# VmeConnectors.net
KiCad netlist of a schematic drawn in Altium Designer
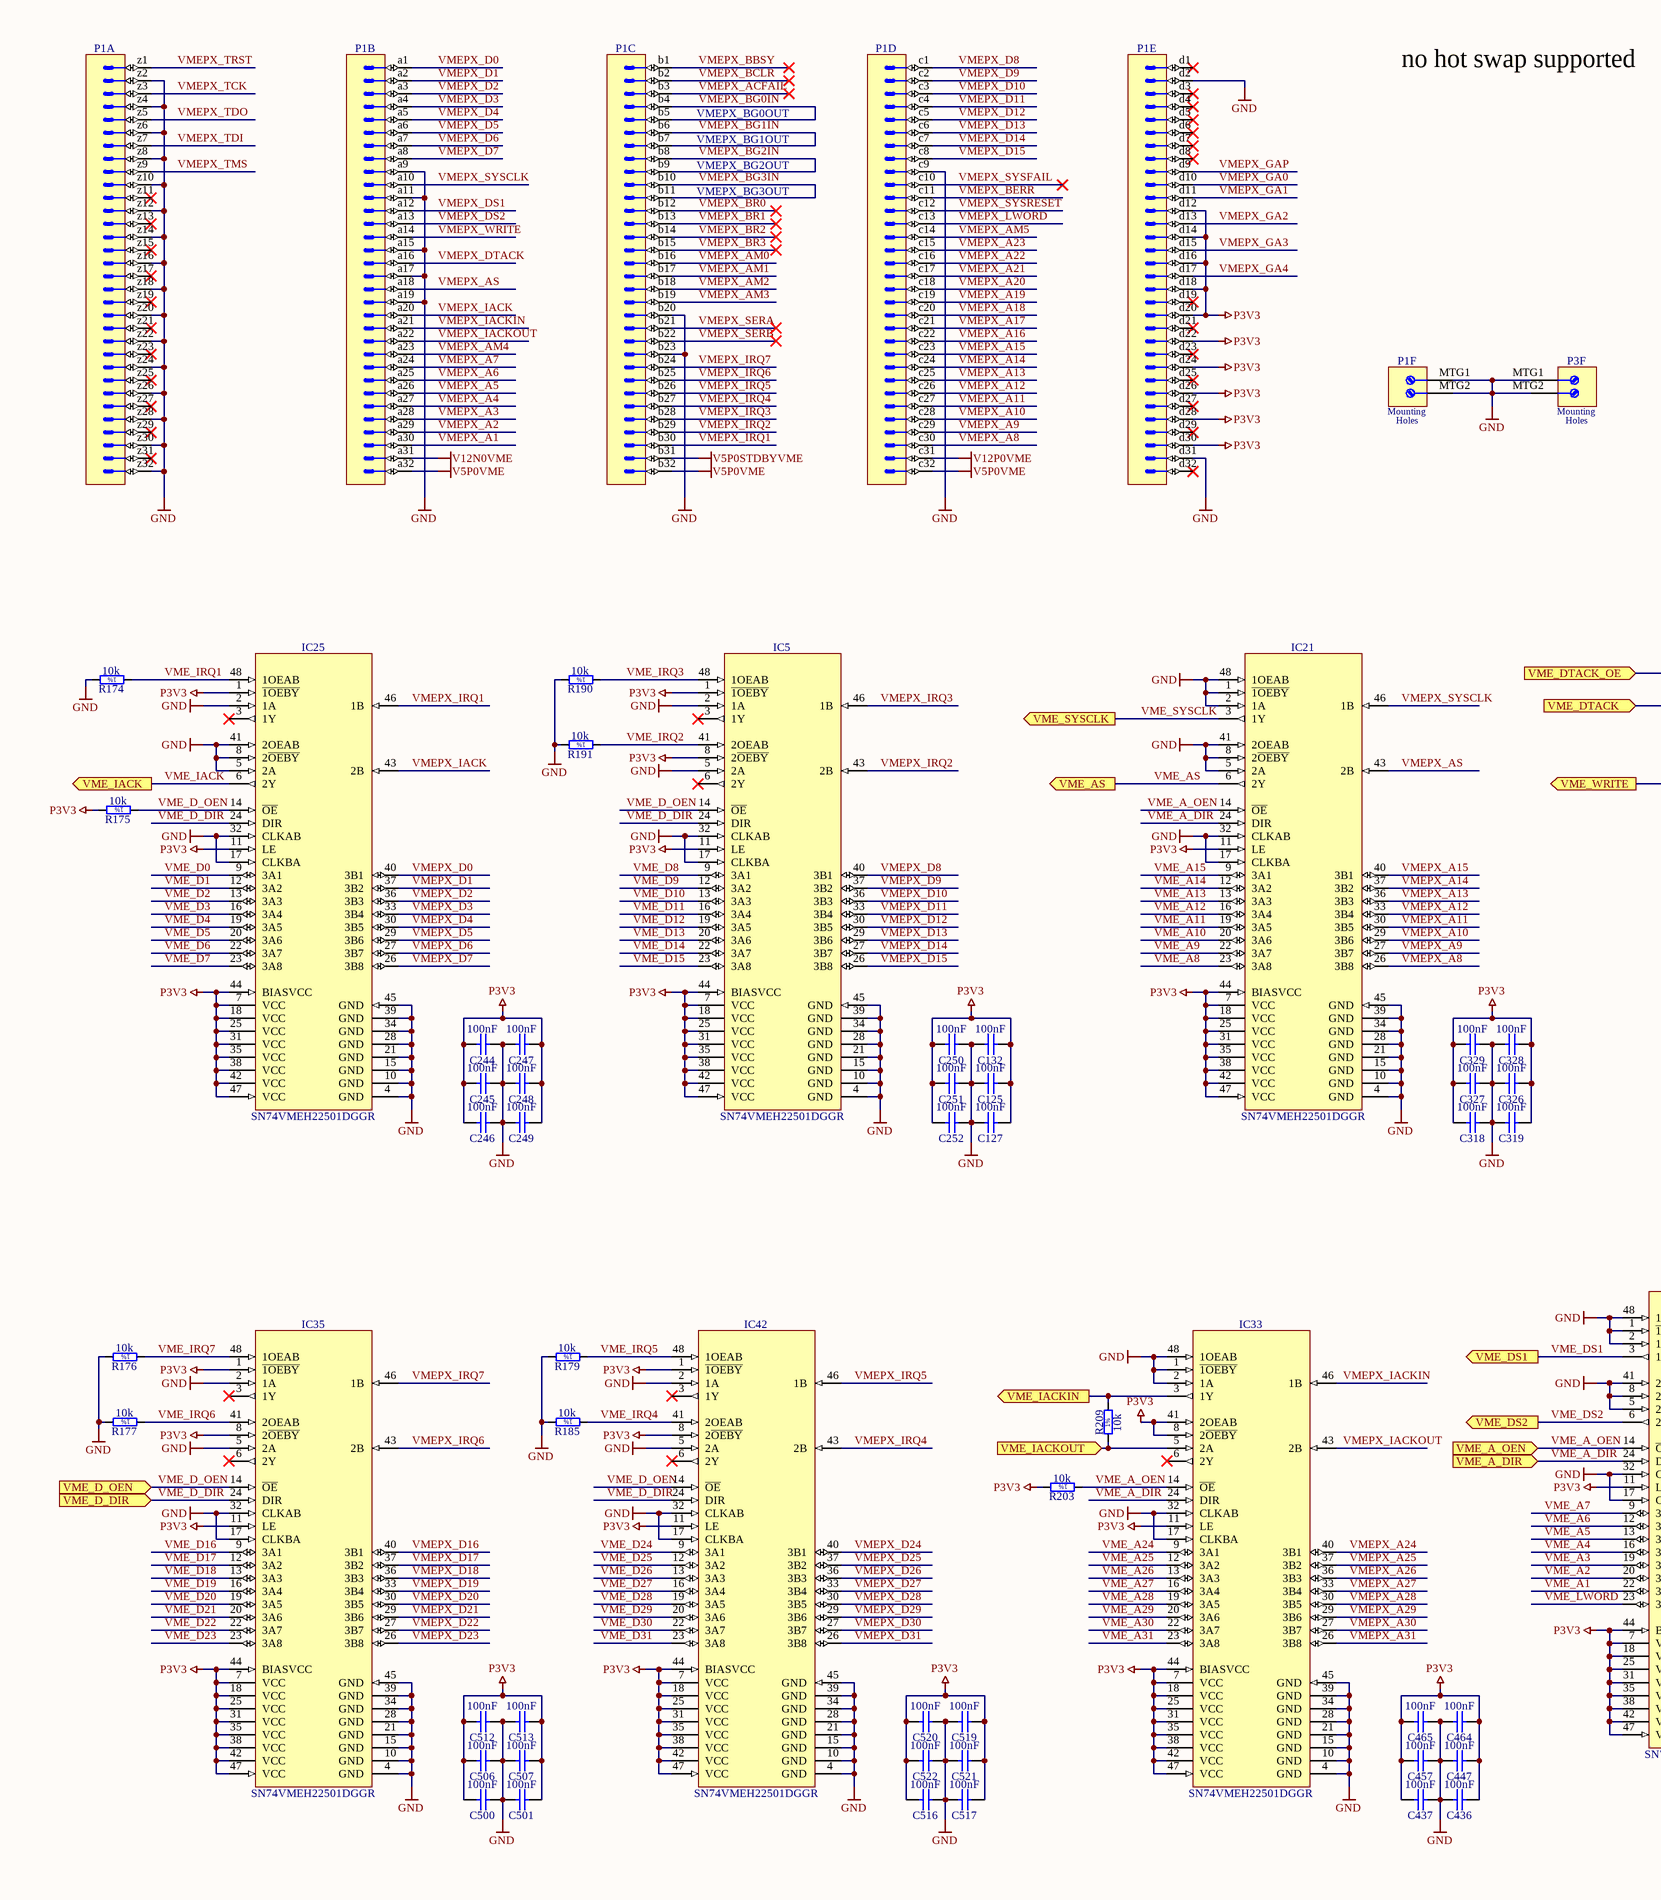
[diagram p0: VmeConnectors.SchDoc, left]
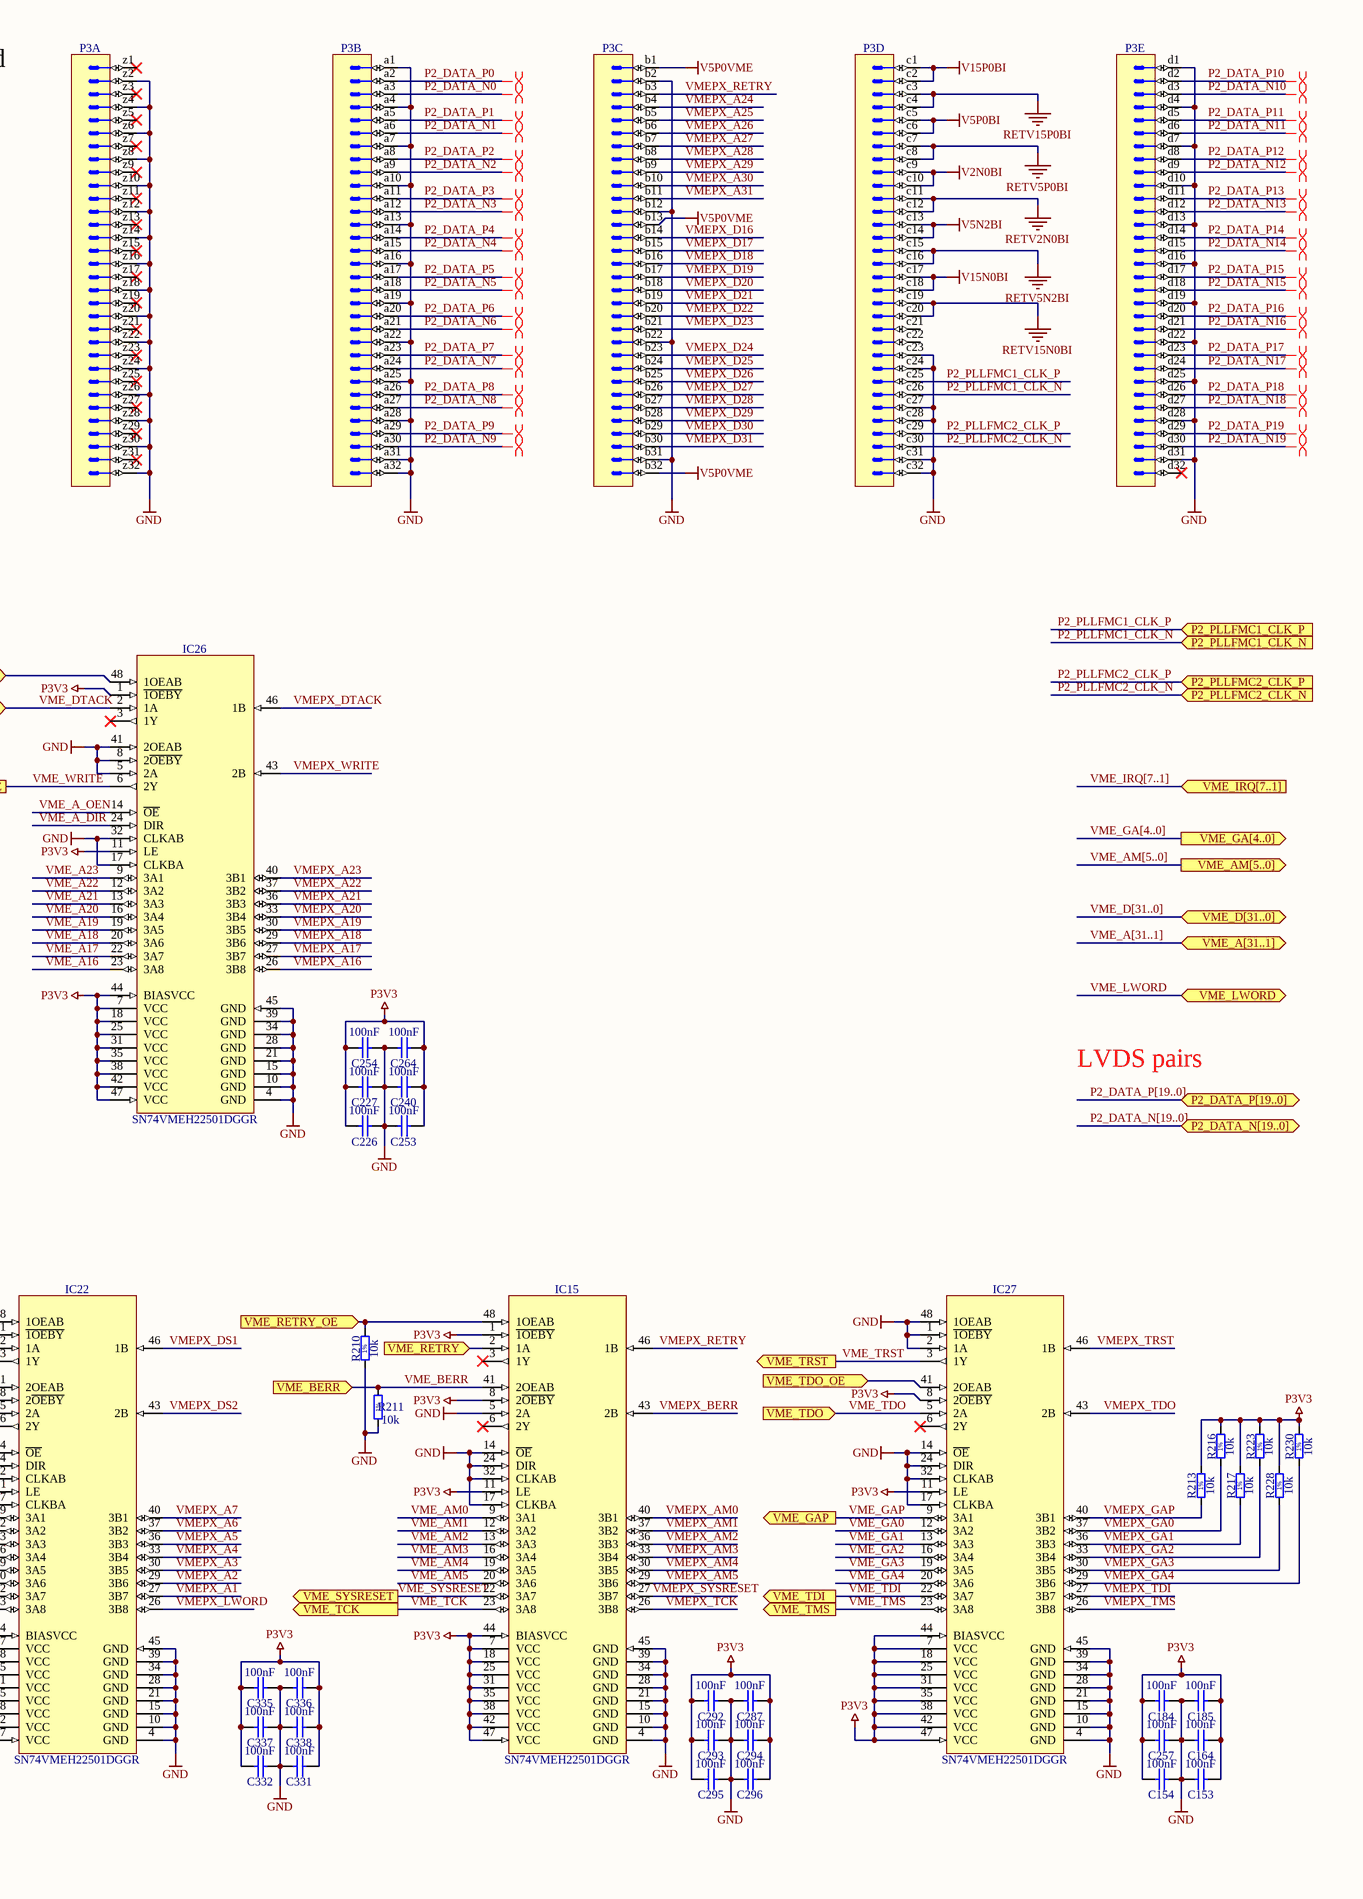
[diagram p1: VmeConnectors.SchDoc, right]

(export (version "E")
  (design (tool "Eeschema 10.0.6"))
  (components
    (comp (ref "C125")
      (value "100nF")
      (footprint "CAPC1005X55N")
      (description "Non-polarised capacitor")
      (fields
        (field (name "PART NUMBER") "CC0402_100NF_16V_10%_X7R")
        (field (name "VOLTAGE") "16V")
        (field (name "AUTHOR") "CERN DEM JLC")
      )
      (libsource (lib "Capacitors") (part "Capacitor - non polarized"))
    )
    (comp (ref "C127")
      (value "100nF")
      (footprint "CAPC1005X55N")
      (description "Non-polarised capacitor")
      (fields
        (field (name "PART NUMBER") "CC0402_100NF_16V_10%_X7R")
        (field (name "VOLTAGE") "16V")
        (field (name "AUTHOR") "CERN DEM JLC")
      )
      (libsource (lib "Capacitors") (part "Capacitor - non polarized"))
    )
    (comp (ref "C132")
      (value "100nF")
      (footprint "CAPC1005X55N")
      (description "Non-polarised capacitor")
      (fields
        (field (name "PART NUMBER") "CC0402_100NF_16V_10%_X7R")
        (field (name "VOLTAGE") "16V")
        (field (name "AUTHOR") "CERN DEM JLC")
      )
      (libsource (lib "Capacitors") (part "Capacitor - non polarized"))
    )
    (comp (ref "C153")
      (value "100nF")
      (footprint "CAPC1005X55N")
      (description "Non-polarised capacitor")
      (fields
        (field (name "PART NUMBER") "CC0402_100NF_16V_10%_X7R")
        (field (name "VOLTAGE") "16V")
        (field (name "AUTHOR") "CERN DEM JLC")
      )
      (libsource (lib "Capacitors") (part "Capacitor - non polarized"))
    )
    (comp (ref "C154")
      (value "100nF")
      (footprint "CAPC1005X55N")
      (description "Non-polarised capacitor")
      (fields
        (field (name "PART NUMBER") "CC0402_100NF_16V_10%_X7R")
        (field (name "VOLTAGE") "16V")
        (field (name "AUTHOR") "CERN DEM JLC")
      )
      (libsource (lib "Capacitors") (part "Capacitor - non polarized"))
    )
    (comp (ref "C164")
      (value "100nF")
      (footprint "CAPC1005X55N")
      (description "Non-polarised capacitor")
      (fields
        (field (name "PART NUMBER") "CC0402_100NF_16V_10%_X7R")
        (field (name "VOLTAGE") "16V")
        (field (name "AUTHOR") "CERN DEM JLC")
      )
      (libsource (lib "Capacitors") (part "Capacitor - non polarized"))
    )
    (comp (ref "C184")
      (value "100nF")
      (footprint "CAPC1005X55N")
      (description "Non-polarised capacitor")
      (fields
        (field (name "PART NUMBER") "CC0402_100NF_16V_10%_X7R")
        (field (name "VOLTAGE") "16V")
        (field (name "AUTHOR") "CERN DEM JLC")
      )
      (libsource (lib "Capacitors") (part "Capacitor - non polarized"))
    )
    (comp (ref "C185")
      (value "100nF")
      (footprint "CAPC1005X55N")
      (description "Non-polarised capacitor")
      (fields
        (field (name "PART NUMBER") "CC0402_100NF_16V_10%_X7R")
        (field (name "VOLTAGE") "16V")
        (field (name "AUTHOR") "CERN DEM JLC")
      )
      (libsource (lib "Capacitors") (part "Capacitor - non polarized"))
    )
    (comp (ref "C226")
      (value "100nF")
      (footprint "CAPC1005X55N")
      (description "Non-polarised capacitor")
      (fields
        (field (name "PART NUMBER") "CC0402_100NF_16V_10%_X7R")
        (field (name "VOLTAGE") "16V")
        (field (name "AUTHOR") "CERN DEM JLC")
      )
      (libsource (lib "Capacitors") (part "Capacitor - non polarized"))
    )
    (comp (ref "C227")
      (value "100nF")
      (footprint "CAPC1005X55N")
      (description "Non-polarised capacitor")
      (fields
        (field (name "PART NUMBER") "CC0402_100NF_16V_10%_X7R")
        (field (name "VOLTAGE") "16V")
        (field (name "AUTHOR") "CERN DEM JLC")
      )
      (libsource (lib "Capacitors") (part "Capacitor - non polarized"))
    )
    (comp (ref "C240")
      (value "100nF")
      (footprint "CAPC1005X55N")
      (description "Non-polarised capacitor")
      (fields
        (field (name "PART NUMBER") "CC0402_100NF_16V_10%_X7R")
        (field (name "VOLTAGE") "16V")
        (field (name "AUTHOR") "CERN DEM JLC")
      )
      (libsource (lib "Capacitors") (part "Capacitor - non polarized"))
    )
    (comp (ref "C244")
      (value "100nF")
      (footprint "CAPC1005X55N")
      (description "Non-polarised capacitor")
      (fields
        (field (name "PART NUMBER") "CC0402_100NF_16V_10%_X7R")
        (field (name "VOLTAGE") "16V")
        (field (name "AUTHOR") "CERN DEM JLC")
      )
      (libsource (lib "Capacitors") (part "Capacitor - non polarized"))
    )
    (comp (ref "C245")
      (value "100nF")
      (footprint "CAPC1005X55N")
      (description "Non-polarised capacitor")
      (fields
        (field (name "PART NUMBER") "CC0402_100NF_16V_10%_X7R")
        (field (name "VOLTAGE") "16V")
        (field (name "AUTHOR") "CERN DEM JLC")
      )
      (libsource (lib "Capacitors") (part "Capacitor - non polarized"))
    )
    (comp (ref "C246")
      (value "100nF")
      (footprint "CAPC1005X55N")
      (description "Non-polarised capacitor")
      (fields
        (field (name "PART NUMBER") "CC0402_100NF_16V_10%_X7R")
        (field (name "VOLTAGE") "16V")
        (field (name "AUTHOR") "CERN DEM JLC")
      )
      (libsource (lib "Capacitors") (part "Capacitor - non polarized"))
    )
    (comp (ref "C247")
      (value "100nF")
      (footprint "CAPC1005X55N")
      (description "Non-polarised capacitor")
      (fields
        (field (name "PART NUMBER") "CC0402_100NF_16V_10%_X7R")
        (field (name "VOLTAGE") "16V")
        (field (name "AUTHOR") "CERN DEM JLC")
      )
      (libsource (lib "Capacitors") (part "Capacitor - non polarized"))
    )
    (comp (ref "C248")
      (value "100nF")
      (footprint "CAPC1005X55N")
      (description "Non-polarised capacitor")
      (fields
        (field (name "PART NUMBER") "CC0402_100NF_16V_10%_X7R")
        (field (name "VOLTAGE") "16V")
        (field (name "AUTHOR") "CERN DEM JLC")
      )
      (libsource (lib "Capacitors") (part "Capacitor - non polarized"))
    )
    (comp (ref "C249")
      (value "100nF")
      (footprint "CAPC1005X55N")
      (description "Non-polarised capacitor")
      (fields
        (field (name "PART NUMBER") "CC0402_100NF_16V_10%_X7R")
        (field (name "VOLTAGE") "16V")
        (field (name "AUTHOR") "CERN DEM JLC")
      )
      (libsource (lib "Capacitors") (part "Capacitor - non polarized"))
    )
    (comp (ref "C250")
      (value "100nF")
      (footprint "CAPC1005X55N")
      (description "Non-polarised capacitor")
      (fields
        (field (name "PART NUMBER") "CC0402_100NF_16V_10%_X7R")
        (field (name "VOLTAGE") "16V")
        (field (name "AUTHOR") "CERN DEM JLC")
      )
      (libsource (lib "Capacitors") (part "Capacitor - non polarized"))
    )
    (comp (ref "C251")
      (value "100nF")
      (footprint "CAPC1005X55N")
      (description "Non-polarised capacitor")
      (fields
        (field (name "PART NUMBER") "CC0402_100NF_16V_10%_X7R")
        (field (name "VOLTAGE") "16V")
        (field (name "AUTHOR") "CERN DEM JLC")
      )
      (libsource (lib "Capacitors") (part "Capacitor - non polarized"))
    )
    (comp (ref "C252")
      (value "100nF")
      (footprint "CAPC1005X55N")
      (description "Non-polarised capacitor")
      (fields
        (field (name "PART NUMBER") "CC0402_100NF_16V_10%_X7R")
        (field (name "VOLTAGE") "16V")
        (field (name "AUTHOR") "CERN DEM JLC")
      )
      (libsource (lib "Capacitors") (part "Capacitor - non polarized"))
    )
    (comp (ref "C253")
      (value "100nF")
      (footprint "CAPC1005X55N")
      (description "Non-polarised capacitor")
      (fields
        (field (name "PART NUMBER") "CC0402_100NF_16V_10%_X7R")
        (field (name "VOLTAGE") "16V")
        (field (name "AUTHOR") "CERN DEM JLC")
      )
      (libsource (lib "Capacitors") (part "Capacitor - non polarized"))
    )
    (comp (ref "C254")
      (value "100nF")
      (footprint "CAPC1005X55N")
      (description "Non-polarised capacitor")
      (fields
        (field (name "PART NUMBER") "CC0402_100NF_16V_10%_X7R")
        (field (name "VOLTAGE") "16V")
        (field (name "AUTHOR") "CERN DEM JLC")
      )
      (libsource (lib "Capacitors") (part "Capacitor - non polarized"))
    )
    (comp (ref "C257")
      (value "100nF")
      (footprint "CAPC1005X55N")
      (description "Non-polarised capacitor")
      (fields
        (field (name "PART NUMBER") "CC0402_100NF_16V_10%_X7R")
        (field (name "VOLTAGE") "16V")
        (field (name "AUTHOR") "CERN DEM JLC")
      )
      (libsource (lib "Capacitors") (part "Capacitor - non polarized"))
    )
    (comp (ref "C264")
      (value "100nF")
      (footprint "CAPC1005X55N")
      (description "Non-polarised capacitor")
      (fields
        (field (name "PART NUMBER") "CC0402_100NF_16V_10%_X7R")
        (field (name "VOLTAGE") "16V")
        (field (name "AUTHOR") "CERN DEM JLC")
      )
      (libsource (lib "Capacitors") (part "Capacitor - non polarized"))
    )
    (comp (ref "C287")
      (value "100nF")
      (footprint "CAPC1005X55N")
      (description "Non-polarised capacitor")
      (fields
        (field (name "PART NUMBER") "CC0402_100NF_16V_10%_X7R")
        (field (name "VOLTAGE") "16V")
        (field (name "AUTHOR") "CERN DEM JLC")
      )
      (libsource (lib "Capacitors") (part "Capacitor - non polarized"))
    )
    (comp (ref "C292")
      (value "100nF")
      (footprint "CAPC1005X55N")
      (description "Non-polarised capacitor")
      (fields
        (field (name "PART NUMBER") "CC0402_100NF_16V_10%_X7R")
        (field (name "VOLTAGE") "16V")
        (field (name "AUTHOR") "CERN DEM JLC")
      )
      (libsource (lib "Capacitors") (part "Capacitor - non polarized"))
    )
    (comp (ref "C293")
      (value "100nF")
      (footprint "CAPC1005X55N")
      (description "Non-polarised capacitor")
      (fields
        (field (name "PART NUMBER") "CC0402_100NF_16V_10%_X7R")
        (field (name "VOLTAGE") "16V")
        (field (name "AUTHOR") "CERN DEM JLC")
      )
      (libsource (lib "Capacitors") (part "Capacitor - non polarized"))
    )
    (comp (ref "C294")
      (value "100nF")
      (footprint "CAPC1005X55N")
      (description "Non-polarised capacitor")
      (fields
        (field (name "PART NUMBER") "CC0402_100NF_16V_10%_X7R")
        (field (name "VOLTAGE") "16V")
        (field (name "AUTHOR") "CERN DEM JLC")
      )
      (libsource (lib "Capacitors") (part "Capacitor - non polarized"))
    )
    (comp (ref "C295")
      (value "100nF")
      (footprint "CAPC1005X55N")
      (description "Non-polarised capacitor")
      (fields
        (field (name "PART NUMBER") "CC0402_100NF_16V_10%_X7R")
        (field (name "VOLTAGE") "16V")
        (field (name "AUTHOR") "CERN DEM JLC")
      )
      (libsource (lib "Capacitors") (part "Capacitor - non polarized"))
    )
    (comp (ref "C296")
      (value "100nF")
      (footprint "CAPC1005X55N")
      (description "Non-polarised capacitor")
      (fields
        (field (name "PART NUMBER") "CC0402_100NF_16V_10%_X7R")
        (field (name "VOLTAGE") "16V")
        (field (name "AUTHOR") "CERN DEM JLC")
      )
      (libsource (lib "Capacitors") (part "Capacitor - non polarized"))
    )
    (comp (ref "C318")
      (value "100nF")
      (footprint "CAPC1005X55N")
      (description "Non-polarised capacitor")
      (fields
        (field (name "PART NUMBER") "CC0402_100NF_16V_10%_X7R")
        (field (name "VOLTAGE") "16V")
        (field (name "AUTHOR") "CERN DEM JLC")
      )
      (libsource (lib "Capacitors") (part "Capacitor - non polarized"))
    )
    (comp (ref "C319")
      (value "100nF")
      (footprint "CAPC1005X55N")
      (description "Non-polarised capacitor")
      (fields
        (field (name "PART NUMBER") "CC0402_100NF_16V_10%_X7R")
        (field (name "VOLTAGE") "16V")
        (field (name "AUTHOR") "CERN DEM JLC")
      )
      (libsource (lib "Capacitors") (part "Capacitor - non polarized"))
    )
    (comp (ref "C326")
      (value "100nF")
      (footprint "CAPC1005X55N")
      (description "Non-polarised capacitor")
      (fields
        (field (name "PART NUMBER") "CC0402_100NF_16V_10%_X7R")
        (field (name "VOLTAGE") "16V")
        (field (name "AUTHOR") "CERN DEM JLC")
      )
      (libsource (lib "Capacitors") (part "Capacitor - non polarized"))
    )
    (comp (ref "C327")
      (value "100nF")
      (footprint "CAPC1005X55N")
      (description "Non-polarised capacitor")
      (fields
        (field (name "PART NUMBER") "CC0402_100NF_16V_10%_X7R")
        (field (name "VOLTAGE") "16V")
        (field (name "AUTHOR") "CERN DEM JLC")
      )
      (libsource (lib "Capacitors") (part "Capacitor - non polarized"))
    )
    (comp (ref "C328")
      (value "100nF")
      (footprint "CAPC1005X55N")
      (description "Non-polarised capacitor")
      (fields
        (field (name "PART NUMBER") "CC0402_100NF_16V_10%_X7R")
        (field (name "VOLTAGE") "16V")
        (field (name "AUTHOR") "CERN DEM JLC")
      )
      (libsource (lib "Capacitors") (part "Capacitor - non polarized"))
    )
    (comp (ref "C329")
      (value "100nF")
      (footprint "CAPC1005X55N")
      (description "Non-polarised capacitor")
      (fields
        (field (name "PART NUMBER") "CC0402_100NF_16V_10%_X7R")
        (field (name "VOLTAGE") "16V")
        (field (name "AUTHOR") "CERN DEM JLC")
      )
      (libsource (lib "Capacitors") (part "Capacitor - non polarized"))
    )
    (comp (ref "C331")
      (value "100nF")
      (footprint "CAPC1005X55N")
      (description "Non-polarised capacitor")
      (fields
        (field (name "PART NUMBER") "CC0402_100NF_16V_10%_X7R")
        (field (name "VOLTAGE") "16V")
        (field (name "AUTHOR") "CERN DEM JLC")
      )
      (libsource (lib "Capacitors") (part "Capacitor - non polarized"))
    )
    (comp (ref "C332")
      (value "100nF")
      (footprint "CAPC1005X55N")
      (description "Non-polarised capacitor")
      (fields
        (field (name "PART NUMBER") "CC0402_100NF_16V_10%_X7R")
        (field (name "VOLTAGE") "16V")
        (field (name "AUTHOR") "CERN DEM JLC")
      )
      (libsource (lib "Capacitors") (part "Capacitor - non polarized"))
    )
    (comp (ref "C335")
      (value "100nF")
      (footprint "CAPC1005X55N")
      (description "Non-polarised capacitor")
      (fields
        (field (name "PART NUMBER") "CC0402_100NF_16V_10%_X7R")
        (field (name "VOLTAGE") "16V")
        (field (name "AUTHOR") "CERN DEM JLC")
      )
      (libsource (lib "Capacitors") (part "Capacitor - non polarized"))
    )
    (comp (ref "C336")
      (value "100nF")
      (footprint "CAPC1005X55N")
      (description "Non-polarised capacitor")
      (fields
        (field (name "PART NUMBER") "CC0402_100NF_16V_10%_X7R")
        (field (name "VOLTAGE") "16V")
        (field (name "AUTHOR") "CERN DEM JLC")
      )
      (libsource (lib "Capacitors") (part "Capacitor - non polarized"))
    )
    (comp (ref "C337")
      (value "100nF")
      (footprint "CAPC1005X55N")
      (description "Non-polarised capacitor")
      (fields
        (field (name "PART NUMBER") "CC0402_100NF_16V_10%_X7R")
        (field (name "VOLTAGE") "16V")
        (field (name "AUTHOR") "CERN DEM JLC")
      )
      (libsource (lib "Capacitors") (part "Capacitor - non polarized"))
    )
    (comp (ref "C338")
      (value "100nF")
      (footprint "CAPC1005X55N")
      (description "Non-polarised capacitor")
      (fields
        (field (name "PART NUMBER") "CC0402_100NF_16V_10%_X7R")
        (field (name "VOLTAGE") "16V")
        (field (name "AUTHOR") "CERN DEM JLC")
      )
      (libsource (lib "Capacitors") (part "Capacitor - non polarized"))
    )
    (comp (ref "C436")
      (value "100nF")
      (footprint "CAPC1005X55N")
      (description "Non-polarised capacitor")
      (fields
        (field (name "PART NUMBER") "CC0402_100NF_16V_10%_X7R")
        (field (name "VOLTAGE") "16V")
        (field (name "AUTHOR") "CERN DEM JLC")
      )
      (libsource (lib "Capacitors") (part "Capacitor - non polarized"))
    )
    (comp (ref "C437")
      (value "100nF")
      (footprint "CAPC1005X55N")
      (description "Non-polarised capacitor")
      (fields
        (field (name "PART NUMBER") "CC0402_100NF_16V_10%_X7R")
        (field (name "VOLTAGE") "16V")
        (field (name "AUTHOR") "CERN DEM JLC")
      )
      (libsource (lib "Capacitors") (part "Capacitor - non polarized"))
    )
    (comp (ref "C447")
      (value "100nF")
      (footprint "CAPC1005X55N")
      (description "Non-polarised capacitor")
      (fields
        (field (name "PART NUMBER") "CC0402_100NF_16V_10%_X7R")
        (field (name "VOLTAGE") "16V")
        (field (name "AUTHOR") "CERN DEM JLC")
      )
      (libsource (lib "Capacitors") (part "Capacitor - non polarized"))
    )
    (comp (ref "C457")
      (value "100nF")
      (footprint "CAPC1005X55N")
      (description "Non-polarised capacitor")
      (fields
        (field (name "PART NUMBER") "CC0402_100NF_16V_10%_X7R")
        (field (name "VOLTAGE") "16V")
        (field (name "AUTHOR") "CERN DEM JLC")
      )
      (libsource (lib "Capacitors") (part "Capacitor - non polarized"))
    )
    (comp (ref "C464")
      (value "100nF")
      (footprint "CAPC1005X55N")
      (description "Non-polarised capacitor")
      (fields
        (field (name "PART NUMBER") "CC0402_100NF_16V_10%_X7R")
        (field (name "VOLTAGE") "16V")
        (field (name "AUTHOR") "CERN DEM JLC")
      )
      (libsource (lib "Capacitors") (part "Capacitor - non polarized"))
    )
    (comp (ref "C465")
      (value "100nF")
      (footprint "CAPC1005X55N")
      (description "Non-polarised capacitor")
      (fields
        (field (name "PART NUMBER") "CC0402_100NF_16V_10%_X7R")
        (field (name "VOLTAGE") "16V")
        (field (name "AUTHOR") "CERN DEM JLC")
      )
      (libsource (lib "Capacitors") (part "Capacitor - non polarized"))
    )
    (comp (ref "C500")
      (value "100nF")
      (footprint "CAPC1005X55N")
      (description "Non-polarised capacitor")
      (fields
        (field (name "PART NUMBER") "CC0402_100NF_16V_10%_X7R")
        (field (name "VOLTAGE") "16V")
        (field (name "AUTHOR") "CERN DEM JLC")
      )
      (libsource (lib "Capacitors") (part "Capacitor - non polarized"))
    )
    (comp (ref "C501")
      (value "100nF")
      (footprint "CAPC1005X55N")
      (description "Non-polarised capacitor")
      (fields
        (field (name "PART NUMBER") "CC0402_100NF_16V_10%_X7R")
        (field (name "VOLTAGE") "16V")
        (field (name "AUTHOR") "CERN DEM JLC")
      )
      (libsource (lib "Capacitors") (part "Capacitor - non polarized"))
    )
    (comp (ref "C506")
      (value "100nF")
      (footprint "CAPC1005X55N")
      (description "Non-polarised capacitor")
      (fields
        (field (name "PART NUMBER") "CC0402_100NF_16V_10%_X7R")
        (field (name "VOLTAGE") "16V")
        (field (name "AUTHOR") "CERN DEM JLC")
      )
      (libsource (lib "Capacitors") (part "Capacitor - non polarized"))
    )
    (comp (ref "C507")
      (value "100nF")
      (footprint "CAPC1005X55N")
      (description "Non-polarised capacitor")
      (fields
        (field (name "PART NUMBER") "CC0402_100NF_16V_10%_X7R")
        (field (name "VOLTAGE") "16V")
        (field (name "AUTHOR") "CERN DEM JLC")
      )
      (libsource (lib "Capacitors") (part "Capacitor - non polarized"))
    )
    (comp (ref "C512")
      (value "100nF")
      (footprint "CAPC1005X55N")
      (description "Non-polarised capacitor")
      (fields
        (field (name "PART NUMBER") "CC0402_100NF_16V_10%_X7R")
        (field (name "VOLTAGE") "16V")
        (field (name "AUTHOR") "CERN DEM JLC")
      )
      (libsource (lib "Capacitors") (part "Capacitor - non polarized"))
    )
    (comp (ref "C513")
      (value "100nF")
      (footprint "CAPC1005X55N")
      (description "Non-polarised capacitor")
      (fields
        (field (name "PART NUMBER") "CC0402_100NF_16V_10%_X7R")
        (field (name "VOLTAGE") "16V")
        (field (name "AUTHOR") "CERN DEM JLC")
      )
      (libsource (lib "Capacitors") (part "Capacitor - non polarized"))
    )
    (comp (ref "C516")
      (value "100nF")
      (footprint "CAPC1005X55N")
      (description "Non-polarised capacitor")
      (fields
        (field (name "PART NUMBER") "CC0402_100NF_16V_10%_X7R")
        (field (name "VOLTAGE") "16V")
        (field (name "AUTHOR") "CERN DEM JLC")
      )
      (libsource (lib "Capacitors") (part "Capacitor - non polarized"))
    )
    (comp (ref "C517")
      (value "100nF")
      (footprint "CAPC1005X55N")
      (description "Non-polarised capacitor")
      (fields
        (field (name "PART NUMBER") "CC0402_100NF_16V_10%_X7R")
        (field (name "VOLTAGE") "16V")
        (field (name "AUTHOR") "CERN DEM JLC")
      )
      (libsource (lib "Capacitors") (part "Capacitor - non polarized"))
    )
    (comp (ref "C519")
      (value "100nF")
      (footprint "CAPC1005X55N")
      (description "Non-polarised capacitor")
      (fields
        (field (name "PART NUMBER") "CC0402_100NF_16V_10%_X7R")
        (field (name "VOLTAGE") "16V")
        (field (name "AUTHOR") "CERN DEM JLC")
      )
      (libsource (lib "Capacitors") (part "Capacitor - non polarized"))
    )
    (comp (ref "C520")
      (value "100nF")
      (footprint "CAPC1005X55N")
      (description "Non-polarised capacitor")
      (fields
        (field (name "PART NUMBER") "CC0402_100NF_16V_10%_X7R")
        (field (name "VOLTAGE") "16V")
        (field (name "AUTHOR") "CERN DEM JLC")
      )
      (libsource (lib "Capacitors") (part "Capacitor - non polarized"))
    )
    (comp (ref "C521")
      (value "100nF")
      (footprint "CAPC1005X55N")
      (description "Non-polarised capacitor")
      (fields
        (field (name "PART NUMBER") "CC0402_100NF_16V_10%_X7R")
        (field (name "VOLTAGE") "16V")
        (field (name "AUTHOR") "CERN DEM JLC")
      )
      (libsource (lib "Capacitors") (part "Capacitor - non polarized"))
    )
    (comp (ref "C522")
      (value "100nF")
      (footprint "CAPC1005X55N")
      (description "Non-polarised capacitor")
      (fields
        (field (name "PART NUMBER") "CC0402_100NF_16V_10%_X7R")
        (field (name "VOLTAGE") "16V")
        (field (name "AUTHOR") "CERN DEM JLC")
      )
      (libsource (lib "Capacitors") (part "Capacitor - non polarized"))
    )
    (comp (ref "IC5")
      (value "SN74VMEH22501DGGR")
      (footprint "SOP50P810X120-48N")
      (description "8-Bit Universal Bus Transceiver and Two 1-Bit Bus Transceivers with 3-State Outputs")
      (fields (field (name "MANUFACTURER") "TEXAS INSTRUMENTS") (field (name "AUTHOR") "CERN DEM JLC"))
      (libsource (lib "ICs And Semiconductors") (part "74VMEH22501"))
    )
    (comp (ref "IC15")
      (value "SN74VMEH22501DGGR")
      (footprint "SOP50P810X120-48N")
      (description "8-Bit Universal Bus Transceiver and Two 1-Bit Bus Transceivers with 3-State Outputs")
      (fields (field (name "MANUFACTURER") "TEXAS INSTRUMENTS") (field (name "AUTHOR") "CERN DEM JLC"))
      (libsource (lib "ICs And Semiconductors") (part "74VMEH22501"))
    )
    (comp (ref "IC21")
      (value "SN74VMEH22501DGGR")
      (footprint "SOP50P810X120-48N")
      (description "8-Bit Universal Bus Transceiver and Two 1-Bit Bus Transceivers with 3-State Outputs")
      (fields (field (name "MANUFACTURER") "TEXAS INSTRUMENTS") (field (name "AUTHOR") "CERN DEM JLC"))
      (libsource (lib "ICs And Semiconductors") (part "74VMEH22501"))
    )
    (comp (ref "IC22")
      (value "SN74VMEH22501DGGR")
      (footprint "SOP50P810X120-48N")
      (description "8-Bit Universal Bus Transceiver and Two 1-Bit Bus Transceivers with 3-State Outputs")
      (fields (field (name "MANUFACTURER") "TEXAS INSTRUMENTS") (field (name "AUTHOR") "CERN DEM JLC"))
      (libsource (lib "ICs And Semiconductors") (part "74VMEH22501"))
    )
    (comp (ref "IC25")
      (value "SN74VMEH22501DGGR")
      (footprint "SOP50P810X120-48N")
      (description "8-Bit Universal Bus Transceiver and Two 1-Bit Bus Transceivers with 3-State Outputs")
      (fields (field (name "MANUFACTURER") "TEXAS INSTRUMENTS") (field (name "AUTHOR") "CERN DEM JLC"))
      (libsource (lib "ICs And Semiconductors") (part "74VMEH22501"))
    )
    (comp (ref "IC26")
      (value "SN74VMEH22501DGGR")
      (footprint "SOP50P810X120-48N")
      (description "8-Bit Universal Bus Transceiver and Two 1-Bit Bus Transceivers with 3-State Outputs")
      (fields (field (name "MANUFACTURER") "TEXAS INSTRUMENTS") (field (name "AUTHOR") "CERN DEM JLC"))
      (libsource (lib "ICs And Semiconductors") (part "74VMEH22501"))
    )
    (comp (ref "IC27")
      (value "SN74VMEH22501DGGR")
      (footprint "SOP50P810X120-48N")
      (description "8-Bit Universal Bus Transceiver and Two 1-Bit Bus Transceivers with 3-State Outputs")
      (fields (field (name "MANUFACTURER") "TEXAS INSTRUMENTS") (field (name "AUTHOR") "CERN DEM JLC"))
      (libsource (lib "ICs And Semiconductors") (part "74VMEH22501"))
    )
    (comp (ref "IC33")
      (value "SN74VMEH22501DGGR")
      (footprint "SOP50P810X120-48N")
      (description "8-Bit Universal Bus Transceiver and Two 1-Bit Bus Transceivers with 3-State Outputs")
      (fields (field (name "MANUFACTURER") "TEXAS INSTRUMENTS") (field (name "AUTHOR") "CERN DEM JLC"))
      (libsource (lib "ICs And Semiconductors") (part "74VMEH22501"))
    )
    (comp (ref "IC35")
      (value "SN74VMEH22501DGGR")
      (footprint "SOP50P810X120-48N")
      (description "8-Bit Universal Bus Transceiver and Two 1-Bit Bus Transceivers with 3-State Outputs")
      (fields (field (name "MANUFACTURER") "TEXAS INSTRUMENTS") (field (name "AUTHOR") "CERN DEM JLC"))
      (libsource (lib "ICs And Semiconductors") (part "74VMEH22501"))
    )
    (comp (ref "IC42")
      (value "SN74VMEH22501DGGR")
      (footprint "SOP50P810X120-48N")
      (description "8-Bit Universal Bus Transceiver and Two 1-Bit Bus Transceivers with 3-State Outputs")
      (fields (field (name "MANUFACTURER") "TEXAS INSTRUMENTS") (field (name "AUTHOR") "CERN DEM JLC"))
      (libsource (lib "ICs And Semiconductors") (part "74VMEH22501"))
    )
    (comp (ref "P1")
      (value "HAR-BUS 64")
      (footprint "HARTING_02 01 160 2101")
      (description "Connector 160zabcd Male (5x32)")
      (fields
        (field (name "PART NUMBER") "HARTING_02 01 160 2101")
        (field (name "MANUFACTURER") "HARTING")
        (field (name "AUTHOR") "CERN DEM JLC")
      )
      (libsource (lib "Connectors") (part "Connector 160zabcd Male (5x32)"))
    )
    (comp (ref "P3")
      (value "HAR-BUS 64")
      (footprint "HARTING_02 01 160 2101")
      (description "Connector 160zabcd Male (5x32)")
      (fields
        (field (name "PART NUMBER") "HARTING_02 01 160 2101")
        (field (name "MANUFACTURER") "HARTING")
        (field (name "AUTHOR") "CERN DEM JLC")
      )
      (libsource (lib "Connectors") (part "Connector 160zabcd Male (5x32)"))
    )
    (comp (ref "R174")
      (value "10k")
      (footprint "RESC1608X55N")
      (description "Resistor - 1%")
      (fields
        (field (name "PART NUMBER") "R0603_10K_1%_0.1W_100PPM")
        (field (name "POWER") "0.1W")
        (field (name "AUTHOR") "CERN DEM JLC")
      )
      (libsource (lib "Resistors") (part "Resistor - 1%"))
    )
    (comp (ref "R175")
      (value "10k")
      (footprint "RESC1608X55N")
      (description "Resistor - 1%")
      (fields
        (field (name "PART NUMBER") "R0603_10K_1%_0.1W_100PPM")
        (field (name "POWER") "0.1W")
        (field (name "AUTHOR") "CERN DEM JLC")
      )
      (libsource (lib "Resistors") (part "Resistor - 1%"))
    )
    (comp (ref "R176")
      (value "10k")
      (footprint "RESC1608X55N")
      (description "Resistor - 1%")
      (fields
        (field (name "PART NUMBER") "R0603_10K_1%_0.1W_100PPM")
        (field (name "POWER") "0.1W")
        (field (name "AUTHOR") "CERN DEM JLC")
      )
      (libsource (lib "Resistors") (part "Resistor - 1%"))
    )
    (comp (ref "R177")
      (value "10k")
      (footprint "RESC1608X55N")
      (description "Resistor - 1%")
      (fields
        (field (name "PART NUMBER") "R0603_10K_1%_0.1W_100PPM")
        (field (name "POWER") "0.1W")
        (field (name "AUTHOR") "CERN DEM JLC")
      )
      (libsource (lib "Resistors") (part "Resistor - 1%"))
    )
    (comp (ref "R179")
      (value "10k")
      (footprint "RESC1608X55N")
      (description "Resistor - 1%")
      (fields
        (field (name "PART NUMBER") "R0603_10K_1%_0.1W_100PPM")
        (field (name "POWER") "0.1W")
        (field (name "AUTHOR") "CERN DEM JLC")
      )
      (libsource (lib "Resistors") (part "Resistor - 1%"))
    )
    (comp (ref "R185")
      (value "10k")
      (footprint "RESC1608X55N")
      (description "Resistor - 1%")
      (fields
        (field (name "PART NUMBER") "R0603_10K_1%_0.1W_100PPM")
        (field (name "POWER") "0.1W")
        (field (name "AUTHOR") "CERN DEM JLC")
      )
      (libsource (lib "Resistors") (part "Resistor - 1%"))
    )
    (comp (ref "R190")
      (value "10k")
      (footprint "RESC1608X55N")
      (description "Resistor - 1%")
      (fields
        (field (name "PART NUMBER") "R0603_10K_1%_0.1W_100PPM")
        (field (name "POWER") "0.1W")
        (field (name "AUTHOR") "CERN DEM JLC")
      )
      (libsource (lib "Resistors") (part "Resistor - 1%"))
    )
    (comp (ref "R191")
      (value "10k")
      (footprint "RESC1608X55N")
      (description "Resistor - 1%")
      (fields
        (field (name "PART NUMBER") "R0603_10K_1%_0.1W_100PPM")
        (field (name "POWER") "0.1W")
        (field (name "AUTHOR") "CERN DEM JLC")
      )
      (libsource (lib "Resistors") (part "Resistor - 1%"))
    )
    (comp (ref "R203")
      (value "10k")
      (footprint "RESC1608X55N")
      (description "Resistor - 1%")
      (fields
        (field (name "PART NUMBER") "R0603_10K_1%_0.1W_100PPM")
        (field (name "POWER") "0.1W")
        (field (name "AUTHOR") "CERN DEM JLC")
      )
      (libsource (lib "Resistors") (part "Resistor - 1%"))
    )
    (comp (ref "R209")
      (value "10k")
      (footprint "RESC1608X55N")
      (description "Resistor - 1%")
      (fields
        (field (name "PART NUMBER") "R0603_10K_1%_0.1W_100PPM")
        (field (name "POWER") "0.1W")
        (field (name "AUTHOR") "CERN DEM JLC")
      )
      (libsource (lib "Resistors") (part "Resistor - 1%"))
    )
    (comp (ref "R210")
      (value "10k")
      (footprint "RESC1608X55N")
      (description "Resistor - 1%")
      (fields
        (field (name "PART NUMBER") "R0603_10K_1%_0.1W_100PPM")
        (field (name "POWER") "0.1W")
        (field (name "AUTHOR") "CERN DEM JLC")
      )
      (libsource (lib "Resistors") (part "Resistor - 1%"))
    )
    (comp (ref "R211")
      (value "10k")
      (footprint "RESC1608X55N")
      (description "Resistor - 1%")
      (fields
        (field (name "PART NUMBER") "R0603_10K_1%_0.1W_100PPM")
        (field (name "POWER") "0.1W")
        (field (name "AUTHOR") "CERN DEM JLC")
      )
      (libsource (lib "Resistors") (part "Resistor - 1%"))
    )
    (comp (ref "R213")
      (value "10k")
      (footprint "RESC1608X55N")
      (description "Resistor - 1%")
      (fields
        (field (name "PART NUMBER") "R0603_10K_1%_0.1W_100PPM")
        (field (name "POWER") "0.1W")
        (field (name "AUTHOR") "CERN DEM JLC")
      )
      (libsource (lib "Resistors") (part "Resistor - 1%"))
    )
    (comp (ref "R216")
      (value "10k")
      (footprint "RESC1608X55N")
      (description "Resistor - 1%")
      (fields
        (field (name "PART NUMBER") "R0603_10K_1%_0.1W_100PPM")
        (field (name "POWER") "0.1W")
        (field (name "AUTHOR") "CERN DEM JLC")
      )
      (libsource (lib "Resistors") (part "Resistor - 1%"))
    )
    (comp (ref "R217")
      (value "10k")
      (footprint "RESC1608X55N")
      (description "Resistor - 1%")
      (fields
        (field (name "PART NUMBER") "R0603_10K_1%_0.1W_100PPM")
        (field (name "POWER") "0.1W")
        (field (name "AUTHOR") "CERN DEM JLC")
      )
      (libsource (lib "Resistors") (part "Resistor - 1%"))
    )
    (comp (ref "R223")
      (value "10k")
      (footprint "RESC1608X55N")
      (description "Resistor - 1%")
      (fields
        (field (name "PART NUMBER") "R0603_10K_1%_0.1W_100PPM")
        (field (name "POWER") "0.1W")
        (field (name "AUTHOR") "CERN DEM JLC")
      )
      (libsource (lib "Resistors") (part "Resistor - 1%"))
    )
    (comp (ref "R228")
      (value "10k")
      (footprint "RESC1608X55N")
      (description "Resistor - 1%")
      (fields
        (field (name "PART NUMBER") "R0603_10K_1%_0.1W_100PPM")
        (field (name "POWER") "0.1W")
        (field (name "AUTHOR") "CERN DEM JLC")
      )
      (libsource (lib "Resistors") (part "Resistor - 1%"))
    )
    (comp (ref "R230")
      (value "10k")
      (footprint "RESC1608X55N")
      (description "Resistor - 1%")
      (fields
        (field (name "PART NUMBER") "R0603_10K_1%_0.1W_100PPM")
        (field (name "POWER") "0.1W")
        (field (name "AUTHOR") "CERN DEM JLC")
      )
      (libsource (lib "Resistors") (part "Resistor - 1%"))
    )
  )
  (nets
    (net (code "1") (name "/P2_DATA_N0") (class "Default")
      (node (ref "P3") (pin "a3") (pinfunction "a3_a3") (pintype "bidirectional"))
    )
    (net (code "2") (name "/P2_DATA_N1") (class "Default")
      (node (ref "P3") (pin "a6") (pinfunction "a6_a6") (pintype "bidirectional"))
    )
    (net (code "3") (name "/P2_DATA_N2") (class "Default")
      (node (ref "P3") (pin "a9") (pinfunction "a9_a9") (pintype "bidirectional"))
    )
    (net (code "4") (name "/P2_DATA_N3") (class "Default")
      (node (ref "P3") (pin "a12") (pinfunction "a12_a12") (pintype "bidirectional"))
    )
    (net (code "5") (name "/P2_DATA_N4") (class "Default")
      (node (ref "P3") (pin "a15") (pinfunction "a15_a15") (pintype "bidirectional"))
    )
    (net (code "6") (name "/P2_DATA_N5") (class "Default")
      (node (ref "P3") (pin "a18") (pinfunction "a18_a18") (pintype "bidirectional"))
    )
    (net (code "7") (name "/P2_DATA_N6") (class "Default")
      (node (ref "P3") (pin "a21") (pinfunction "a21_a21") (pintype "bidirectional"))
    )
    (net (code "8") (name "/P2_DATA_N7") (class "Default")
      (node (ref "P3") (pin "a24") (pinfunction "a24_a24") (pintype "bidirectional"))
    )
    (net (code "9") (name "/P2_DATA_N8") (class "Default")
      (node (ref "P3") (pin "a27") (pinfunction "a27_a27") (pintype "bidirectional"))
    )
    (net (code "10") (name "/P2_DATA_N9") (class "Default")
      (node (ref "P3") (pin "a30") (pinfunction "a30_a30") (pintype "bidirectional"))
    )
    (net (code "11") (name "/P2_DATA_N10") (class "Default")
      (node (ref "P3") (pin "d3") (pinfunction "d3_d3") (pintype "bidirectional"))
    )
    (net (code "12") (name "/P2_DATA_N11") (class "Default")
      (node (ref "P3") (pin "d6") (pinfunction "d6_d6") (pintype "bidirectional"))
    )
    (net (code "13") (name "/P2_DATA_N12") (class "Default")
      (node (ref "P3") (pin "d9") (pinfunction "d9_d9") (pintype "bidirectional"))
    )
    (net (code "14") (name "/P2_DATA_N13") (class "Default")
      (node (ref "P3") (pin "d12") (pinfunction "d12_d12") (pintype "bidirectional"))
    )
    (net (code "15") (name "/P2_DATA_N14") (class "Default")
      (node (ref "P3") (pin "d15") (pinfunction "d15_d15") (pintype "bidirectional"))
    )
    (net (code "16") (name "/P2_DATA_N15") (class "Default")
      (node (ref "P3") (pin "d18") (pinfunction "d18_d18") (pintype "bidirectional"))
    )
    (net (code "17") (name "/P2_DATA_N16") (class "Default")
      (node (ref "P3") (pin "d21") (pinfunction "d21_d21") (pintype "bidirectional"))
    )
    (net (code "18") (name "/P2_DATA_N17") (class "Default")
      (node (ref "P3") (pin "d24") (pinfunction "d24_d24") (pintype "bidirectional"))
    )
    (net (code "19") (name "/P2_DATA_N18") (class "Default")
      (node (ref "P3") (pin "d27") (pinfunction "d27_d27") (pintype "bidirectional"))
    )
    (net (code "20") (name "/P2_DATA_N19") (class "Default")
      (node (ref "P3") (pin "d30") (pinfunction "d30_d30") (pintype "bidirectional"))
    )
    (net (code "22") (name "/P2_DATA_P0") (class "Default")
      (node (ref "P3") (pin "a2") (pinfunction "a2_a2") (pintype "bidirectional"))
    )
    (net (code "23") (name "/P2_DATA_P1") (class "Default")
      (node (ref "P3") (pin "a5") (pinfunction "a5_a5") (pintype "bidirectional"))
    )
    (net (code "24") (name "/P2_DATA_P2") (class "Default")
      (node (ref "P3") (pin "a8") (pinfunction "a8_a8") (pintype "bidirectional"))
    )
    (net (code "25") (name "/P2_DATA_P3") (class "Default")
      (node (ref "P3") (pin "a11") (pinfunction "a11_a11") (pintype "bidirectional"))
    )
    (net (code "26") (name "/P2_DATA_P4") (class "Default")
      (node (ref "P3") (pin "a14") (pinfunction "a14_a14") (pintype "bidirectional"))
    )
    (net (code "27") (name "/P2_DATA_P5") (class "Default")
      (node (ref "P3") (pin "a17") (pinfunction "a17_a17") (pintype "bidirectional"))
    )
    (net (code "28") (name "/P2_DATA_P6") (class "Default")
      (node (ref "P3") (pin "a20") (pinfunction "a20_a20") (pintype "bidirectional"))
    )
    (net (code "29") (name "/P2_DATA_P7") (class "Default")
      (node (ref "P3") (pin "a23") (pinfunction "a23_a23") (pintype "bidirectional"))
    )
    (net (code "30") (name "/P2_DATA_P8") (class "Default")
      (node (ref "P3") (pin "a26") (pinfunction "a26_a26") (pintype "bidirectional"))
    )
    (net (code "31") (name "/P2_DATA_P9") (class "Default")
      (node (ref "P3") (pin "a29") (pinfunction "a29_a29") (pintype "bidirectional"))
    )
    (net (code "32") (name "/P2_DATA_P10") (class "Default")
      (node (ref "P3") (pin "d2") (pinfunction "d2_d2") (pintype "bidirectional"))
    )
    (net (code "33") (name "/P2_DATA_P11") (class "Default")
      (node (ref "P3") (pin "d5") (pinfunction "d5_d5") (pintype "bidirectional"))
    )
    (net (code "34") (name "/P2_DATA_P12") (class "Default")
      (node (ref "P3") (pin "d8") (pinfunction "d8_d8") (pintype "bidirectional"))
    )
    (net (code "35") (name "/P2_DATA_P13") (class "Default")
      (node (ref "P3") (pin "d11") (pinfunction "d11_d11") (pintype "bidirectional"))
    )
    (net (code "36") (name "/P2_DATA_P14") (class "Default")
      (node (ref "P3") (pin "d14") (pinfunction "d14_d14") (pintype "bidirectional"))
    )
    (net (code "37") (name "/P2_DATA_P15") (class "Default")
      (node (ref "P3") (pin "d17") (pinfunction "d17_d17") (pintype "bidirectional"))
    )
    (net (code "38") (name "/P2_DATA_P16") (class "Default")
      (node (ref "P3") (pin "d20") (pinfunction "d20_d20") (pintype "bidirectional"))
    )
    (net (code "39") (name "/P2_DATA_P17") (class "Default")
      (node (ref "P3") (pin "d23") (pinfunction "d23_d23") (pintype "bidirectional"))
    )
    (net (code "40") (name "/P2_DATA_P18") (class "Default")
      (node (ref "P3") (pin "d26") (pinfunction "d26_d26") (pintype "bidirectional"))
    )
    (net (code "41") (name "/P2_DATA_P19") (class "Default")
      (node (ref "P3") (pin "d29") (pinfunction "d29_d29") (pintype "bidirectional"))
    )
    (net (code "43") (name "/P2_PLLFMC1_CLK_N") (class "Default")
      (node (ref "P3") (pin "c26") (pinfunction "c26_c26") (pintype "bidirectional"))
    )
    (net (code "44") (name "/P2_PLLFMC1_CLK_P") (class "Default")
      (node (ref "P3") (pin "c25") (pinfunction "c25_c25") (pintype "bidirectional"))
    )
    (net (code "45") (name "/P2_PLLFMC2_CLK_N") (class "Default")
      (node (ref "P3") (pin "c30") (pinfunction "c30_c30") (pintype "bidirectional"))
    )
    (net (code "46") (name "/P2_PLLFMC2_CLK_P") (class "Default")
      (node (ref "P3") (pin "c29") (pinfunction "c29_c29") (pintype "bidirectional"))
    )
    (net (code "47") (name "/VMEPX_A1") (class "Default")
      (node (ref "IC22") (pin "27") (pinfunction "3B7_27") (pintype "bidirectional"))
      (node (ref "P1") (pin "a30") (pinfunction "a30_a30") (pintype "bidirectional"))
    )
    (net (code "48") (name "/VMEPX_A2") (class "Default")
      (node (ref "IC22") (pin "29") (pinfunction "3B6_29") (pintype "bidirectional"))
      (node (ref "P1") (pin "a29") (pinfunction "a29_a29") (pintype "bidirectional"))
    )
    (net (code "49") (name "/VMEPX_A3") (class "Default")
      (node (ref "IC22") (pin "30") (pinfunction "3B5_30") (pintype "bidirectional"))
      (node (ref "P1") (pin "a28") (pinfunction "a28_a28") (pintype "bidirectional"))
    )
    (net (code "50") (name "/VMEPX_A4") (class "Default")
      (node (ref "IC22") (pin "33") (pinfunction "3B4_33") (pintype "bidirectional"))
      (node (ref "P1") (pin "a27") (pinfunction "a27_a27") (pintype "bidirectional"))
    )
    (net (code "51") (name "/VMEPX_A5") (class "Default")
      (node (ref "IC22") (pin "36") (pinfunction "3B3_36") (pintype "bidirectional"))
      (node (ref "P1") (pin "a26") (pinfunction "a26_a26") (pintype "bidirectional"))
    )
    (net (code "52") (name "/VMEPX_A6") (class "Default")
      (node (ref "IC22") (pin "37") (pinfunction "3B2_37") (pintype "bidirectional"))
      (node (ref "P1") (pin "a25") (pinfunction "a25_a25") (pintype "bidirectional"))
    )
    (net (code "53") (name "/VMEPX_A7") (class "Default")
      (node (ref "IC22") (pin "40") (pinfunction "3B1_40") (pintype "bidirectional"))
      (node (ref "P1") (pin "a24") (pinfunction "a24_a24") (pintype "bidirectional"))
    )
    (net (code "54") (name "/VMEPX_A8") (class "Default")
      (node (ref "IC21") (pin "26") (pinfunction "3B8_26") (pintype "bidirectional"))
      (node (ref "P1") (pin "c30") (pinfunction "c30_c30") (pintype "bidirectional"))
    )
    (net (code "55") (name "/VMEPX_A9") (class "Default")
      (node (ref "IC21") (pin "27") (pinfunction "3B7_27") (pintype "bidirectional"))
      (node (ref "P1") (pin "c29") (pinfunction "c29_c29") (pintype "bidirectional"))
    )
    (net (code "56") (name "/VMEPX_A10") (class "Default")
      (node (ref "IC21") (pin "29") (pinfunction "3B6_29") (pintype "bidirectional"))
      (node (ref "P1") (pin "c28") (pinfunction "c28_c28") (pintype "bidirectional"))
    )
    (net (code "57") (name "/VMEPX_A11") (class "Default")
      (node (ref "IC21") (pin "30") (pinfunction "3B5_30") (pintype "bidirectional"))
      (node (ref "P1") (pin "c27") (pinfunction "c27_c27") (pintype "bidirectional"))
    )
    (net (code "58") (name "/VMEPX_A12") (class "Default")
      (node (ref "IC21") (pin "33") (pinfunction "3B4_33") (pintype "bidirectional"))
      (node (ref "P1") (pin "c26") (pinfunction "c26_c26") (pintype "bidirectional"))
    )
    (net (code "59") (name "/VMEPX_A13") (class "Default")
      (node (ref "IC21") (pin "36") (pinfunction "3B3_36") (pintype "bidirectional"))
      (node (ref "P1") (pin "c25") (pinfunction "c25_c25") (pintype "bidirectional"))
    )
    (net (code "60") (name "/VMEPX_A14") (class "Default")
      (node (ref "IC21") (pin "37") (pinfunction "3B2_37") (pintype "bidirectional"))
      (node (ref "P1") (pin "c24") (pinfunction "c24_c24") (pintype "bidirectional"))
    )
    (net (code "61") (name "/VMEPX_A15") (class "Default")
      (node (ref "IC21") (pin "40") (pinfunction "3B1_40") (pintype "bidirectional"))
      (node (ref "P1") (pin "c23") (pinfunction "c23_c23") (pintype "bidirectional"))
    )
    (net (code "62") (name "/VMEPX_A16") (class "Default")
      (node (ref "IC26") (pin "26") (pinfunction "3B8_26") (pintype "bidirectional"))
      (node (ref "P1") (pin "c22") (pinfunction "c22_c22") (pintype "bidirectional"))
    )
    (net (code "63") (name "/VMEPX_A17") (class "Default")
      (node (ref "IC26") (pin "27") (pinfunction "3B7_27") (pintype "bidirectional"))
      (node (ref "P1") (pin "c21") (pinfunction "c21_c21") (pintype "bidirectional"))
    )
    (net (code "64") (name "/VMEPX_A18") (class "Default")
      (node (ref "IC26") (pin "29") (pinfunction "3B6_29") (pintype "bidirectional"))
      (node (ref "P1") (pin "c20") (pinfunction "c20_c20") (pintype "bidirectional"))
    )
    (net (code "65") (name "/VMEPX_A19") (class "Default")
      (node (ref "IC26") (pin "30") (pinfunction "3B5_30") (pintype "bidirectional"))
      (node (ref "P1") (pin "c19") (pinfunction "c19_c19") (pintype "bidirectional"))
    )
    (net (code "66") (name "/VMEPX_A20") (class "Default")
      (node (ref "IC26") (pin "33") (pinfunction "3B4_33") (pintype "bidirectional"))
      (node (ref "P1") (pin "c18") (pinfunction "c18_c18") (pintype "bidirectional"))
    )
    (net (code "67") (name "/VMEPX_A21") (class "Default")
      (node (ref "IC26") (pin "36") (pinfunction "3B3_36") (pintype "bidirectional"))
      (node (ref "P1") (pin "c17") (pinfunction "c17_c17") (pintype "bidirectional"))
    )
    (net (code "68") (name "/VMEPX_A22") (class "Default")
      (node (ref "IC26") (pin "37") (pinfunction "3B2_37") (pintype "bidirectional"))
      (node (ref "P1") (pin "c16") (pinfunction "c16_c16") (pintype "bidirectional"))
    )
    (net (code "69") (name "/VMEPX_A23") (class "Default")
      (node (ref "IC26") (pin "40") (pinfunction "3B1_40") (pintype "bidirectional"))
      (node (ref "P1") (pin "c15") (pinfunction "c15_c15") (pintype "bidirectional"))
    )
    (net (code "70") (name "/VMEPX_A24") (class "Default")
      (node (ref "IC33") (pin "40") (pinfunction "3B1_40") (pintype "bidirectional"))
      (node (ref "P3") (pin "b4") (pinfunction "b4_b4") (pintype "bidirectional"))
    )
    (net (code "71") (name "/VMEPX_A25") (class "Default")
      (node (ref "IC33") (pin "37") (pinfunction "3B2_37") (pintype "bidirectional"))
      (node (ref "P3") (pin "b5") (pinfunction "b5_b5") (pintype "bidirectional"))
    )
    (net (code "72") (name "/VMEPX_A26") (class "Default")
      (node (ref "IC33") (pin "36") (pinfunction "3B3_36") (pintype "bidirectional"))
      (node (ref "P3") (pin "b6") (pinfunction "b6_b6") (pintype "bidirectional"))
    )
    (net (code "73") (name "/VMEPX_A27") (class "Default")
      (node (ref "IC33") (pin "33") (pinfunction "3B4_33") (pintype "bidirectional"))
      (node (ref "P3") (pin "b7") (pinfunction "b7_b7") (pintype "bidirectional"))
    )
    (net (code "74") (name "/VMEPX_A28") (class "Default")
      (node (ref "IC33") (pin "30") (pinfunction "3B5_30") (pintype "bidirectional"))
      (node (ref "P3") (pin "b8") (pinfunction "b8_b8") (pintype "bidirectional"))
    )
    (net (code "75") (name "/VMEPX_A29") (class "Default")
      (node (ref "IC33") (pin "29") (pinfunction "3B6_29") (pintype "bidirectional"))
      (node (ref "P3") (pin "b9") (pinfunction "b9_b9") (pintype "bidirectional"))
    )
    (net (code "76") (name "/VMEPX_A30") (class "Default")
      (node (ref "IC33") (pin "27") (pinfunction "3B7_27") (pintype "bidirectional"))
      (node (ref "P3") (pin "b10") (pinfunction "b10_b10") (pintype "bidirectional"))
    )
    (net (code "77") (name "/VMEPX_A31") (class "Default")
      (node (ref "IC33") (pin "26") (pinfunction "3B8_26") (pintype "bidirectional"))
      (node (ref "P3") (pin "b11") (pinfunction "b11_b11") (pintype "bidirectional"))
    )
    (net (code "78") (name "/VMEPX_ACFAIL") (class "Default")
      (node (ref "P1") (pin "b3") (pinfunction "b3_b3") (pintype "bidirectional+no_connect"))
    )
    (net (code "79") (name "/VMEPX_AM0") (class "Default")
      (node (ref "IC15") (pin "40") (pinfunction "3B1_40") (pintype "bidirectional"))
      (node (ref "P1") (pin "b16") (pinfunction "b16_b16") (pintype "bidirectional"))
    )
    (net (code "80") (name "/VMEPX_AM1") (class "Default")
      (node (ref "IC15") (pin "37") (pinfunction "3B2_37") (pintype "bidirectional"))
      (node (ref "P1") (pin "b17") (pinfunction "b17_b17") (pintype "bidirectional"))
    )
    (net (code "81") (name "/VMEPX_AM2") (class "Default")
      (node (ref "IC15") (pin "36") (pinfunction "3B3_36") (pintype "bidirectional"))
      (node (ref "P1") (pin "b18") (pinfunction "b18_b18") (pintype "bidirectional"))
    )
    (net (code "82") (name "/VMEPX_AM3") (class "Default")
      (node (ref "IC15") (pin "33") (pinfunction "3B4_33") (pintype "bidirectional"))
      (node (ref "P1") (pin "b19") (pinfunction "b19_b19") (pintype "bidirectional"))
    )
    (net (code "83") (name "/VMEPX_AM4") (class "Default")
      (node (ref "IC15") (pin "30") (pinfunction "3B5_30") (pintype "bidirectional"))
      (node (ref "P1") (pin "a23") (pinfunction "a23_a23") (pintype "bidirectional"))
    )
    (net (code "84") (name "/VMEPX_AM5") (class "Default")
      (node (ref "IC15") (pin "29") (pinfunction "3B6_29") (pintype "bidirectional"))
      (node (ref "P1") (pin "c14") (pinfunction "c14_c14") (pintype "bidirectional"))
    )
    (net (code "85") (name "/VMEPX_AS") (class "Default")
      (node (ref "IC21") (pin "43") (pinfunction "2B_43") (pintype "input"))
      (node (ref "P1") (pin "a18") (pinfunction "a18_a18") (pintype "bidirectional"))
    )
    (net (code "86") (name "/VMEPX_BBSY") (class "Default")
      (node (ref "P1") (pin "b1") (pinfunction "b1_b1") (pintype "bidirectional+no_connect"))
    )
    (net (code "87") (name "/VMEPX_BCLR") (class "Default")
      (node (ref "P1") (pin "b2") (pinfunction "b2_b2") (pintype "bidirectional+no_connect"))
    )
    (net (code "88") (name "/VMEPX_BERR") (class "Default")
      (node (ref "IC15") (pin "43") (pinfunction "2B_43") (pintype "input"))
      (node (ref "P1") (pin "c11") (pinfunction "c11_c11") (pintype "bidirectional"))
    )
    (net (code "89") (name "/VMEPX_BG0IN") (class "Default")
      (node (ref "P1") (pin "b4") (pinfunction "b4_b4") (pintype "bidirectional"))
      (node (ref "P1") (pin "b5") (pinfunction "b5_b5") (pintype "bidirectional"))
    )
    (net (code "90") (name "/VMEPX_BG1IN") (class "Default")
      (node (ref "P1") (pin "b6") (pinfunction "b6_b6") (pintype "bidirectional"))
      (node (ref "P1") (pin "b7") (pinfunction "b7_b7") (pintype "bidirectional"))
    )
    (net (code "91") (name "/VMEPX_BG2IN") (class "Default")
      (node (ref "P1") (pin "b8") (pinfunction "b8_b8") (pintype "bidirectional"))
      (node (ref "P1") (pin "b9") (pinfunction "b9_b9") (pintype "bidirectional"))
    )
    (net (code "92") (name "/VMEPX_BG3IN") (class "Default")
      (node (ref "P1") (pin "b10") (pinfunction "b10_b10") (pintype "bidirectional"))
      (node (ref "P1") (pin "b11") (pinfunction "b11_b11") (pintype "bidirectional"))
    )
    (net (code "93") (name "/VMEPX_BR0") (class "Default")
      (node (ref "P1") (pin "b12") (pinfunction "b12_b12") (pintype "bidirectional+no_connect"))
    )
    (net (code "94") (name "/VMEPX_BR1") (class "Default")
      (node (ref "P1") (pin "b13") (pinfunction "b13_b13") (pintype "bidirectional+no_connect"))
    )
    (net (code "95") (name "/VMEPX_BR2") (class "Default")
      (node (ref "P1") (pin "b14") (pinfunction "b14_b14") (pintype "bidirectional+no_connect"))
    )
    (net (code "96") (name "/VMEPX_BR3") (class "Default")
      (node (ref "P1") (pin "b15") (pinfunction "b15_b15") (pintype "bidirectional+no_connect"))
    )
    (net (code "97") (name "/VMEPX_D0") (class "Default")
      (node (ref "IC25") (pin "40") (pinfunction "3B1_40") (pintype "bidirectional"))
      (node (ref "P1") (pin "a1") (pinfunction "a1_a1") (pintype "bidirectional"))
    )
    (net (code "98") (name "/VMEPX_D1") (class "Default")
      (node (ref "IC25") (pin "37") (pinfunction "3B2_37") (pintype "bidirectional"))
      (node (ref "P1") (pin "a2") (pinfunction "a2_a2") (pintype "bidirectional"))
    )
    (net (code "99") (name "/VMEPX_D2") (class "Default")
      (node (ref "IC25") (pin "36") (pinfunction "3B3_36") (pintype "bidirectional"))
      (node (ref "P1") (pin "a3") (pinfunction "a3_a3") (pintype "bidirectional"))
    )
    (net (code "100") (name "/VMEPX_D3") (class "Default")
      (node (ref "IC25") (pin "33") (pinfunction "3B4_33") (pintype "bidirectional"))
      (node (ref "P1") (pin "a4") (pinfunction "a4_a4") (pintype "bidirectional"))
    )
    (net (code "101") (name "/VMEPX_D4") (class "Default")
      (node (ref "IC25") (pin "30") (pinfunction "3B5_30") (pintype "bidirectional"))
      (node (ref "P1") (pin "a5") (pinfunction "a5_a5") (pintype "bidirectional"))
    )
    (net (code "102") (name "/VMEPX_D5") (class "Default")
      (node (ref "IC25") (pin "29") (pinfunction "3B6_29") (pintype "bidirectional"))
      (node (ref "P1") (pin "a6") (pinfunction "a6_a6") (pintype "bidirectional"))
    )
    (net (code "103") (name "/VMEPX_D6") (class "Default")
      (node (ref "IC25") (pin "27") (pinfunction "3B7_27") (pintype "bidirectional"))
      (node (ref "P1") (pin "a7") (pinfunction "a7_a7") (pintype "bidirectional"))
    )
    (net (code "104") (name "/VMEPX_D7") (class "Default")
      (node (ref "IC25") (pin "26") (pinfunction "3B8_26") (pintype "bidirectional"))
      (node (ref "P1") (pin "a8") (pinfunction "a8_a8") (pintype "bidirectional"))
    )
    (net (code "105") (name "/VMEPX_D8") (class "Default")
      (node (ref "IC5") (pin "40") (pinfunction "3B1_40") (pintype "bidirectional"))
      (node (ref "P1") (pin "c1") (pinfunction "c1_c1") (pintype "bidirectional"))
    )
    (net (code "106") (name "/VMEPX_D9") (class "Default")
      (node (ref "IC5") (pin "37") (pinfunction "3B2_37") (pintype "bidirectional"))
      (node (ref "P1") (pin "c2") (pinfunction "c2_c2") (pintype "bidirectional"))
    )
    (net (code "107") (name "/VMEPX_D10") (class "Default")
      (node (ref "IC5") (pin "36") (pinfunction "3B3_36") (pintype "bidirectional"))
      (node (ref "P1") (pin "c3") (pinfunction "c3_c3") (pintype "bidirectional"))
    )
    (net (code "108") (name "/VMEPX_D11") (class "Default")
      (node (ref "IC5") (pin "33") (pinfunction "3B4_33") (pintype "bidirectional"))
      (node (ref "P1") (pin "c4") (pinfunction "c4_c4") (pintype "bidirectional"))
    )
    (net (code "109") (name "/VMEPX_D12") (class "Default")
      (node (ref "IC5") (pin "30") (pinfunction "3B5_30") (pintype "bidirectional"))
      (node (ref "P1") (pin "c5") (pinfunction "c5_c5") (pintype "bidirectional"))
    )
    (net (code "110") (name "/VMEPX_D13") (class "Default")
      (node (ref "IC5") (pin "29") (pinfunction "3B6_29") (pintype "bidirectional"))
      (node (ref "P1") (pin "c6") (pinfunction "c6_c6") (pintype "bidirectional"))
    )
    (net (code "111") (name "/VMEPX_D14") (class "Default")
      (node (ref "IC5") (pin "27") (pinfunction "3B7_27") (pintype "bidirectional"))
      (node (ref "P1") (pin "c7") (pinfunction "c7_c7") (pintype "bidirectional"))
    )
    (net (code "112") (name "/VMEPX_D15") (class "Default")
      (node (ref "IC5") (pin "26") (pinfunction "3B8_26") (pintype "bidirectional"))
      (node (ref "P1") (pin "c8") (pinfunction "c8_c8") (pintype "bidirectional"))
    )
    (net (code "113") (name "/VMEPX_D16") (class "Default")
      (node (ref "IC35") (pin "40") (pinfunction "3B1_40") (pintype "bidirectional"))
      (node (ref "P3") (pin "b14") (pinfunction "b14_b14") (pintype "bidirectional"))
    )
    (net (code "114") (name "/VMEPX_D17") (class "Default")
      (node (ref "IC35") (pin "37") (pinfunction "3B2_37") (pintype "bidirectional"))
      (node (ref "P3") (pin "b15") (pinfunction "b15_b15") (pintype "bidirectional"))
    )
    (net (code "115") (name "/VMEPX_D18") (class "Default")
      (node (ref "IC35") (pin "36") (pinfunction "3B3_36") (pintype "bidirectional"))
      (node (ref "P3") (pin "b16") (pinfunction "b16_b16") (pintype "bidirectional"))
    )
    (net (code "116") (name "/VMEPX_D19") (class "Default")
      (node (ref "IC35") (pin "33") (pinfunction "3B4_33") (pintype "bidirectional"))
      (node (ref "P3") (pin "b17") (pinfunction "b17_b17") (pintype "bidirectional"))
    )
    (net (code "117") (name "/VMEPX_D20") (class "Default")
      (node (ref "IC35") (pin "30") (pinfunction "3B5_30") (pintype "bidirectional"))
      (node (ref "P3") (pin "b18") (pinfunction "b18_b18") (pintype "bidirectional"))
    )
    (net (code "118") (name "/VMEPX_D21") (class "Default")
      (node (ref "IC35") (pin "29") (pinfunction "3B6_29") (pintype "bidirectional"))
      (node (ref "P3") (pin "b19") (pinfunction "b19_b19") (pintype "bidirectional"))
    )
    (net (code "119") (name "/VMEPX_D22") (class "Default")
      (node (ref "IC35") (pin "27") (pinfunction "3B7_27") (pintype "bidirectional"))
      (node (ref "P3") (pin "b20") (pinfunction "b20_b20") (pintype "bidirectional"))
    )
    (net (code "120") (name "/VMEPX_D23") (class "Default")
      (node (ref "IC35") (pin "26") (pinfunction "3B8_26") (pintype "bidirectional"))
      (node (ref "P3") (pin "b21") (pinfunction "b21_b21") (pintype "bidirectional"))
    )
    (net (code "121") (name "/VMEPX_D24") (class "Default")
      (node (ref "IC42") (pin "40") (pinfunction "3B1_40") (pintype "bidirectional"))
      (node (ref "P3") (pin "b23") (pinfunction "b23_b23") (pintype "bidirectional"))
    )
    (net (code "122") (name "/VMEPX_D25") (class "Default")
      (node (ref "IC42") (pin "37") (pinfunction "3B2_37") (pintype "bidirectional"))
      (node (ref "P3") (pin "b24") (pinfunction "b24_b24") (pintype "bidirectional"))
    )
    (net (code "123") (name "/VMEPX_D26") (class "Default")
      (node (ref "IC42") (pin "36") (pinfunction "3B3_36") (pintype "bidirectional"))
      (node (ref "P3") (pin "b25") (pinfunction "b25_b25") (pintype "bidirectional"))
    )
    (net (code "124") (name "/VMEPX_D27") (class "Default")
      (node (ref "IC42") (pin "33") (pinfunction "3B4_33") (pintype "bidirectional"))
      (node (ref "P3") (pin "b26") (pinfunction "b26_b26") (pintype "bidirectional"))
    )
    (net (code "125") (name "/VMEPX_D28") (class "Default")
      (node (ref "IC42") (pin "30") (pinfunction "3B5_30") (pintype "bidirectional"))
      (node (ref "P3") (pin "b27") (pinfunction "b27_b27") (pintype "bidirectional"))
    )
    (net (code "126") (name "/VMEPX_D29") (class "Default")
      (node (ref "IC42") (pin "29") (pinfunction "3B6_29") (pintype "bidirectional"))
      (node (ref "P3") (pin "b28") (pinfunction "b28_b28") (pintype "bidirectional"))
    )
    (net (code "127") (name "/VMEPX_D30") (class "Default")
      (node (ref "IC42") (pin "27") (pinfunction "3B7_27") (pintype "bidirectional"))
      (node (ref "P3") (pin "b29") (pinfunction "b29_b29") (pintype "bidirectional"))
    )
    (net (code "128") (name "/VMEPX_D31") (class "Default")
      (node (ref "IC42") (pin "26") (pinfunction "3B8_26") (pintype "bidirectional"))
      (node (ref "P3") (pin "b30") (pinfunction "b30_b30") (pintype "bidirectional"))
    )
    (net (code "129") (name "/VMEPX_DS1") (class "Default")
      (node (ref "IC22") (pin "46") (pinfunction "1B_46") (pintype "input"))
      (node (ref "P1") (pin "a12") (pinfunction "a12_a12") (pintype "bidirectional"))
    )
    (net (code "130") (name "/VMEPX_DS2") (class "Default")
      (node (ref "IC22") (pin "43") (pinfunction "2B_43") (pintype "input"))
      (node (ref "P1") (pin "a13") (pinfunction "a13_a13") (pintype "bidirectional"))
    )
    (net (code "131") (name "/VMEPX_DTACK") (class "Default")
      (node (ref "IC26") (pin "46") (pinfunction "1B_46") (pintype "input"))
      (node (ref "P1") (pin "a16") (pinfunction "a16_a16") (pintype "bidirectional"))
    )
    (net (code "132") (name "/VMEPX_GA0") (class "Default")
      (node (ref "IC27") (pin "37") (pinfunction "3B2_37") (pintype "bidirectional"))
      (node (ref "P1") (pin "d10") (pinfunction "d10_d10") (pintype "bidirectional"))
      (node (ref "R216") (pin "1") (pinfunction "1_1") (pintype "passive"))
    )
    (net (code "133") (name "/VMEPX_GA1") (class "Default")
      (node (ref "IC27") (pin "36") (pinfunction "3B3_36") (pintype "bidirectional"))
      (node (ref "P1") (pin "d11") (pinfunction "d11_d11") (pintype "bidirectional"))
      (node (ref "R217") (pin "1") (pinfunction "1_1") (pintype "passive"))
    )
    (net (code "134") (name "/VMEPX_GA2") (class "Default")
      (node (ref "IC27") (pin "33") (pinfunction "3B4_33") (pintype "bidirectional"))
      (node (ref "P1") (pin "d13") (pinfunction "d13_d13") (pintype "bidirectional"))
      (node (ref "R223") (pin "1") (pinfunction "1_1") (pintype "passive"))
    )
    (net (code "135") (name "/VMEPX_GA3") (class "Default")
      (node (ref "IC27") (pin "30") (pinfunction "3B5_30") (pintype "bidirectional"))
      (node (ref "P1") (pin "d15") (pinfunction "d15_d15") (pintype "bidirectional"))
      (node (ref "R228") (pin "1") (pinfunction "1_1") (pintype "passive"))
    )
    (net (code "136") (name "/VMEPX_GA4") (class "Default")
      (node (ref "IC27") (pin "29") (pinfunction "3B6_29") (pintype "bidirectional"))
      (node (ref "P1") (pin "d17") (pinfunction "d17_d17") (pintype "bidirectional"))
      (node (ref "R230") (pin "1") (pinfunction "1_1") (pintype "passive"))
    )
    (net (code "137") (name "/VMEPX_GAP") (class "Default")
      (node (ref "IC27") (pin "40") (pinfunction "3B1_40") (pintype "bidirectional"))
      (node (ref "P1") (pin "d9") (pinfunction "d9_d9") (pintype "bidirectional"))
      (node (ref "R213") (pin "1") (pinfunction "1_1") (pintype "passive"))
    )
    (net (code "138") (name "/VMEPX_IACK") (class "Default")
      (node (ref "IC25") (pin "43") (pinfunction "2B_43") (pintype "input"))
      (node (ref "P1") (pin "a20") (pinfunction "a20_a20") (pintype "bidirectional"))
    )
    (net (code "139") (name "/VMEPX_IACKIN") (class "Default")
      (node (ref "IC33") (pin "46") (pinfunction "1B_46") (pintype "input"))
      (node (ref "P1") (pin "a21") (pinfunction "a21_a21") (pintype "bidirectional"))
    )
    (net (code "140") (name "/VMEPX_IACKOUT") (class "Default")
      (node (ref "IC33") (pin "43") (pinfunction "2B_43") (pintype "input"))
      (node (ref "P1") (pin "a22") (pinfunction "a22_a22") (pintype "bidirectional"))
    )
    (net (code "141") (name "/VMEPX_IRQ1") (class "Default")
      (node (ref "IC25") (pin "46") (pinfunction "1B_46") (pintype "input"))
      (node (ref "P1") (pin "b30") (pinfunction "b30_b30") (pintype "bidirectional"))
    )
    (net (code "142") (name "/VMEPX_IRQ2") (class "Default")
      (node (ref "IC5") (pin "43") (pinfunction "2B_43") (pintype "input"))
      (node (ref "P1") (pin "b29") (pinfunction "b29_b29") (pintype "bidirectional"))
    )
    (net (code "143") (name "/VMEPX_IRQ3") (class "Default")
      (node (ref "IC5") (pin "46") (pinfunction "1B_46") (pintype "input"))
      (node (ref "P1") (pin "b28") (pinfunction "b28_b28") (pintype "bidirectional"))
    )
    (net (code "144") (name "/VMEPX_IRQ4") (class "Default")
      (node (ref "IC42") (pin "43") (pinfunction "2B_43") (pintype "input"))
      (node (ref "P1") (pin "b27") (pinfunction "b27_b27") (pintype "bidirectional"))
    )
    (net (code "145") (name "/VMEPX_IRQ5") (class "Default")
      (node (ref "IC42") (pin "46") (pinfunction "1B_46") (pintype "input"))
      (node (ref "P1") (pin "b26") (pinfunction "b26_b26") (pintype "bidirectional"))
    )
    (net (code "146") (name "/VMEPX_IRQ6") (class "Default")
      (node (ref "IC35") (pin "43") (pinfunction "2B_43") (pintype "input"))
      (node (ref "P1") (pin "b25") (pinfunction "b25_b25") (pintype "bidirectional"))
    )
    (net (code "147") (name "/VMEPX_IRQ7") (class "Default")
      (node (ref "IC35") (pin "46") (pinfunction "1B_46") (pintype "input"))
      (node (ref "P1") (pin "b24") (pinfunction "b24_b24") (pintype "bidirectional"))
    )
    (net (code "148") (name "/VMEPX_LWORD") (class "Default")
      (node (ref "IC22") (pin "26") (pinfunction "3B8_26") (pintype "bidirectional"))
      (node (ref "P1") (pin "c13") (pinfunction "c13_c13") (pintype "bidirectional"))
    )
    (net (code "149") (name "/VMEPX_RETRY") (class "Default")
      (node (ref "IC15") (pin "46") (pinfunction "1B_46") (pintype "input"))
      (node (ref "P3") (pin "b3") (pinfunction "b3_b3") (pintype "bidirectional"))
    )
    (net (code "150") (name "/VMEPX_SERA") (class "Default")
      (node (ref "P1") (pin "b21") (pinfunction "b21_b21") (pintype "bidirectional+no_connect"))
    )
    (net (code "151") (name "/VMEPX_SERB") (class "Default")
      (node (ref "P1") (pin "b22") (pinfunction "b22_b22") (pintype "bidirectional+no_connect"))
    )
    (net (code "152") (name "/VMEPX_SYSCLK") (class "Default")
      (node (ref "IC21") (pin "46") (pinfunction "1B_46") (pintype "input"))
      (node (ref "P1") (pin "a10") (pinfunction "a10_a10") (pintype "bidirectional"))
    )
    (net (code "153") (name "/VMEPX_SYSFAIL") (class "Default")
      (node (ref "P1") (pin "c10") (pinfunction "c10_c10") (pintype "bidirectional+no_connect"))
    )
    (net (code "154") (name "/VMEPX_SYSRESET") (class "Default")
      (node (ref "IC15") (pin "27") (pinfunction "3B7_27") (pintype "bidirectional"))
      (node (ref "P1") (pin "c12") (pinfunction "c12_c12") (pintype "bidirectional"))
    )
    (net (code "155") (name "/VMEPX_TCK") (class "Default")
      (node (ref "IC15") (pin "26") (pinfunction "3B8_26") (pintype "bidirectional"))
      (node (ref "P1") (pin "z3") (pinfunction "z3_z3") (pintype "bidirectional"))
    )
    (net (code "156") (name "/VMEPX_TDI") (class "Default")
      (node (ref "IC27") (pin "27") (pinfunction "3B7_27") (pintype "bidirectional"))
      (node (ref "P1") (pin "z7") (pinfunction "z7_z7") (pintype "bidirectional"))
    )
    (net (code "157") (name "/VMEPX_TDO") (class "Default")
      (node (ref "IC27") (pin "43") (pinfunction "2B_43") (pintype "input"))
      (node (ref "P1") (pin "z5") (pinfunction "z5_z5") (pintype "bidirectional"))
    )
    (net (code "158") (name "/VMEPX_TMS") (class "Default")
      (node (ref "IC27") (pin "26") (pinfunction "3B8_26") (pintype "bidirectional"))
      (node (ref "P1") (pin "z9") (pinfunction "z9_z9") (pintype "bidirectional"))
    )
    (net (code "159") (name "/VMEPX_TRST") (class "Default")
      (node (ref "IC27") (pin "46") (pinfunction "1B_46") (pintype "input"))
      (node (ref "P1") (pin "z1") (pinfunction "z1_z1") (pintype "bidirectional"))
    )
    (net (code "160") (name "/VMEPX_WRITE") (class "Default")
      (node (ref "IC26") (pin "43") (pinfunction "2B_43") (pintype "input"))
      (node (ref "P1") (pin "a14") (pinfunction "a14_a14") (pintype "bidirectional"))
    )
    (net (code "161") (name "/VME_A1") (class "Default")
      (node (ref "IC22") (pin "22") (pinfunction "3A7_22") (pintype "bidirectional"))
    )
    (net (code "162") (name "/VME_A2") (class "Default")
      (node (ref "IC22") (pin "20") (pinfunction "3A6_20") (pintype "bidirectional"))
    )
    (net (code "163") (name "/VME_A3") (class "Default")
      (node (ref "IC22") (pin "19") (pinfunction "3A5_19") (pintype "bidirectional"))
    )
    (net (code "164") (name "/VME_A4") (class "Default")
      (node (ref "IC22") (pin "16") (pinfunction "3A4_16") (pintype "bidirectional"))
    )
    (net (code "165") (name "/VME_A5") (class "Default")
      (node (ref "IC22") (pin "13") (pinfunction "3A3_13") (pintype "bidirectional"))
    )
    (net (code "166") (name "/VME_A6") (class "Default")
      (node (ref "IC22") (pin "12") (pinfunction "3A2_12") (pintype "bidirectional"))
    )
    (net (code "167") (name "/VME_A7") (class "Default")
      (node (ref "IC22") (pin "9") (pinfunction "3A1_9") (pintype "bidirectional"))
    )
    (net (code "168") (name "/VME_A8") (class "Default")
      (node (ref "IC21") (pin "23") (pinfunction "3A8_23") (pintype "bidirectional"))
    )
    (net (code "169") (name "/VME_A9") (class "Default")
      (node (ref "IC21") (pin "22") (pinfunction "3A7_22") (pintype "bidirectional"))
    )
    (net (code "170") (name "/VME_A10") (class "Default")
      (node (ref "IC21") (pin "20") (pinfunction "3A6_20") (pintype "bidirectional"))
    )
    (net (code "171") (name "/VME_A11") (class "Default")
      (node (ref "IC21") (pin "19") (pinfunction "3A5_19") (pintype "bidirectional"))
    )
    (net (code "172") (name "/VME_A12") (class "Default")
      (node (ref "IC21") (pin "16") (pinfunction "3A4_16") (pintype "bidirectional"))
    )
    (net (code "173") (name "/VME_A13") (class "Default")
      (node (ref "IC21") (pin "13") (pinfunction "3A3_13") (pintype "bidirectional"))
    )
    (net (code "174") (name "/VME_A14") (class "Default")
      (node (ref "IC21") (pin "12") (pinfunction "3A2_12") (pintype "bidirectional"))
    )
    (net (code "175") (name "/VME_A15") (class "Default")
      (node (ref "IC21") (pin "9") (pinfunction "3A1_9") (pintype "bidirectional"))
    )
    (net (code "176") (name "/VME_A16") (class "Default")
      (node (ref "IC26") (pin "23") (pinfunction "3A8_23") (pintype "bidirectional"))
    )
    (net (code "177") (name "/VME_A17") (class "Default")
      (node (ref "IC26") (pin "22") (pinfunction "3A7_22") (pintype "bidirectional"))
    )
    (net (code "178") (name "/VME_A18") (class "Default")
      (node (ref "IC26") (pin "20") (pinfunction "3A6_20") (pintype "bidirectional"))
    )
    (net (code "179") (name "/VME_A19") (class "Default")
      (node (ref "IC26") (pin "19") (pinfunction "3A5_19") (pintype "bidirectional"))
    )
    (net (code "180") (name "/VME_A20") (class "Default")
      (node (ref "IC26") (pin "16") (pinfunction "3A4_16") (pintype "bidirectional"))
    )
    (net (code "181") (name "/VME_A21") (class "Default")
      (node (ref "IC26") (pin "13") (pinfunction "3A3_13") (pintype "bidirectional"))
    )
    (net (code "182") (name "/VME_A22") (class "Default")
      (node (ref "IC26") (pin "12") (pinfunction "3A2_12") (pintype "bidirectional"))
    )
    (net (code "183") (name "/VME_A23") (class "Default")
      (node (ref "IC26") (pin "9") (pinfunction "3A1_9") (pintype "bidirectional"))
    )
    (net (code "184") (name "/VME_A24") (class "Default")
      (node (ref "IC33") (pin "9") (pinfunction "3A1_9") (pintype "bidirectional"))
    )
    (net (code "185") (name "/VME_A25") (class "Default")
      (node (ref "IC33") (pin "12") (pinfunction "3A2_12") (pintype "bidirectional"))
    )
    (net (code "186") (name "/VME_A26") (class "Default")
      (node (ref "IC33") (pin "13") (pinfunction "3A3_13") (pintype "bidirectional"))
    )
    (net (code "187") (name "/VME_A27") (class "Default")
      (node (ref "IC33") (pin "16") (pinfunction "3A4_16") (pintype "bidirectional"))
    )
    (net (code "188") (name "/VME_A28") (class "Default")
      (node (ref "IC33") (pin "19") (pinfunction "3A5_19") (pintype "bidirectional"))
    )
    (net (code "189") (name "/VME_A29") (class "Default")
      (node (ref "IC33") (pin "20") (pinfunction "3A6_20") (pintype "bidirectional"))
    )
    (net (code "190") (name "/VME_A30") (class "Default")
      (node (ref "IC33") (pin "22") (pinfunction "3A7_22") (pintype "bidirectional"))
    )
    (net (code "191") (name "/VME_A31") (class "Default")
      (node (ref "IC33") (pin "23") (pinfunction "3A8_23") (pintype "bidirectional"))
    )
    (net (code "192") (name "/VME_AM0") (class "Default")
      (node (ref "IC15") (pin "9") (pinfunction "3A1_9") (pintype "bidirectional"))
    )
    (net (code "193") (name "/VME_AM1") (class "Default")
      (node (ref "IC15") (pin "12") (pinfunction "3A2_12") (pintype "bidirectional"))
    )
    (net (code "194") (name "/VME_AM2") (class "Default")
      (node (ref "IC15") (pin "13") (pinfunction "3A3_13") (pintype "bidirectional"))
    )
    (net (code "195") (name "/VME_AM3") (class "Default")
      (node (ref "IC15") (pin "16") (pinfunction "3A4_16") (pintype "bidirectional"))
    )
    (net (code "196") (name "/VME_AM4") (class "Default")
      (node (ref "IC15") (pin "19") (pinfunction "3A5_19") (pintype "bidirectional"))
    )
    (net (code "197") (name "/VME_AM5") (class "Default")
      (node (ref "IC15") (pin "20") (pinfunction "3A6_20") (pintype "bidirectional"))
    )
    (net (code "199") (name "/VME_AS") (class "Default")
      (node (ref "IC21") (pin "6") (pinfunction "2Y_6") (pintype "output"))
    )
    (net (code "201") (name "/VME_A_DIR") (class "Default")
      (node (ref "IC21") (pin "24") (pinfunction "DIR_24") (pintype "input"))
      (node (ref "IC22") (pin "24") (pinfunction "DIR_24") (pintype "input"))
      (node (ref "IC26") (pin "24") (pinfunction "DIR_24") (pintype "input"))
      (node (ref "IC33") (pin "24") (pinfunction "DIR_24") (pintype "input"))
    )
    (net (code "202") (name "/VME_A_OEN") (class "Default")
      (node (ref "IC21") (pin "14") (pinfunction "~{OE}_14") (pintype "input"))
      (node (ref "IC22") (pin "14") (pinfunction "~{OE}_14") (pintype "input"))
      (node (ref "IC26") (pin "14") (pinfunction "~{OE}_14") (pintype "input"))
      (node (ref "IC33") (pin "14") (pinfunction "~{OE}_14") (pintype "input"))
      (node (ref "R203") (pin "1") (pinfunction "1_1") (pintype "passive"))
    )
    (net (code "203") (name "/VME_BERR") (class "Default")
      (node (ref "IC15") (pin "41") (pinfunction "2OEAB_41") (pintype "input"))
      (node (ref "R211") (pin "2") (pinfunction "2_2") (pintype "passive"))
    )
    (net (code "204") (name "/VME_D0") (class "Default")
      (node (ref "IC25") (pin "9") (pinfunction "3A1_9") (pintype "bidirectional"))
    )
    (net (code "205") (name "/VME_D1") (class "Default")
      (node (ref "IC25") (pin "12") (pinfunction "3A2_12") (pintype "bidirectional"))
    )
    (net (code "206") (name "/VME_D2") (class "Default")
      (node (ref "IC25") (pin "13") (pinfunction "3A3_13") (pintype "bidirectional"))
    )
    (net (code "207") (name "/VME_D3") (class "Default")
      (node (ref "IC25") (pin "16") (pinfunction "3A4_16") (pintype "bidirectional"))
    )
    (net (code "208") (name "/VME_D4") (class "Default")
      (node (ref "IC25") (pin "19") (pinfunction "3A5_19") (pintype "bidirectional"))
    )
    (net (code "209") (name "/VME_D5") (class "Default")
      (node (ref "IC25") (pin "20") (pinfunction "3A6_20") (pintype "bidirectional"))
    )
    (net (code "210") (name "/VME_D6") (class "Default")
      (node (ref "IC25") (pin "22") (pinfunction "3A7_22") (pintype "bidirectional"))
    )
    (net (code "211") (name "/VME_D7") (class "Default")
      (node (ref "IC25") (pin "23") (pinfunction "3A8_23") (pintype "bidirectional"))
    )
    (net (code "212") (name "/VME_D8") (class "Default")
      (node (ref "IC5") (pin "9") (pinfunction "3A1_9") (pintype "bidirectional"))
    )
    (net (code "213") (name "/VME_D9") (class "Default")
      (node (ref "IC5") (pin "12") (pinfunction "3A2_12") (pintype "bidirectional"))
    )
    (net (code "214") (name "/VME_D10") (class "Default")
      (node (ref "IC5") (pin "13") (pinfunction "3A3_13") (pintype "bidirectional"))
    )
    (net (code "215") (name "/VME_D11") (class "Default")
      (node (ref "IC5") (pin "16") (pinfunction "3A4_16") (pintype "bidirectional"))
    )
    (net (code "216") (name "/VME_D12") (class "Default")
      (node (ref "IC5") (pin "19") (pinfunction "3A5_19") (pintype "bidirectional"))
    )
    (net (code "217") (name "/VME_D13") (class "Default")
      (node (ref "IC5") (pin "20") (pinfunction "3A6_20") (pintype "bidirectional"))
    )
    (net (code "218") (name "/VME_D14") (class "Default")
      (node (ref "IC5") (pin "22") (pinfunction "3A7_22") (pintype "bidirectional"))
    )
    (net (code "219") (name "/VME_D15") (class "Default")
      (node (ref "IC5") (pin "23") (pinfunction "3A8_23") (pintype "bidirectional"))
    )
    (net (code "220") (name "/VME_D16") (class "Default")
      (node (ref "IC35") (pin "9") (pinfunction "3A1_9") (pintype "bidirectional"))
    )
    (net (code "221") (name "/VME_D17") (class "Default")
      (node (ref "IC35") (pin "12") (pinfunction "3A2_12") (pintype "bidirectional"))
    )
    (net (code "222") (name "/VME_D18") (class "Default")
      (node (ref "IC35") (pin "13") (pinfunction "3A3_13") (pintype "bidirectional"))
    )
    (net (code "223") (name "/VME_D19") (class "Default")
      (node (ref "IC35") (pin "16") (pinfunction "3A4_16") (pintype "bidirectional"))
    )
    (net (code "224") (name "/VME_D20") (class "Default")
      (node (ref "IC35") (pin "19") (pinfunction "3A5_19") (pintype "bidirectional"))
    )
    (net (code "225") (name "/VME_D21") (class "Default")
      (node (ref "IC35") (pin "20") (pinfunction "3A6_20") (pintype "bidirectional"))
    )
    (net (code "226") (name "/VME_D22") (class "Default")
      (node (ref "IC35") (pin "22") (pinfunction "3A7_22") (pintype "bidirectional"))
    )
    (net (code "227") (name "/VME_D23") (class "Default")
      (node (ref "IC35") (pin "23") (pinfunction "3A8_23") (pintype "bidirectional"))
    )
    (net (code "228") (name "/VME_D24") (class "Default")
      (node (ref "IC42") (pin "9") (pinfunction "3A1_9") (pintype "bidirectional"))
    )
    (net (code "229") (name "/VME_D25") (class "Default")
      (node (ref "IC42") (pin "12") (pinfunction "3A2_12") (pintype "bidirectional"))
    )
    (net (code "230") (name "/VME_D26") (class "Default")
      (node (ref "IC42") (pin "13") (pinfunction "3A3_13") (pintype "bidirectional"))
    )
    (net (code "231") (name "/VME_D27") (class "Default")
      (node (ref "IC42") (pin "16") (pinfunction "3A4_16") (pintype "bidirectional"))
    )
    (net (code "232") (name "/VME_D28") (class "Default")
      (node (ref "IC42") (pin "19") (pinfunction "3A5_19") (pintype "bidirectional"))
    )
    (net (code "233") (name "/VME_D29") (class "Default")
      (node (ref "IC42") (pin "20") (pinfunction "3A6_20") (pintype "bidirectional"))
    )
    (net (code "234") (name "/VME_D30") (class "Default")
      (node (ref "IC42") (pin "22") (pinfunction "3A7_22") (pintype "bidirectional"))
    )
    (net (code "235") (name "/VME_D31") (class "Default")
      (node (ref "IC42") (pin "23") (pinfunction "3A8_23") (pintype "bidirectional"))
    )
    (net (code "236") (name "/VME_DS1") (class "Default")
      (node (ref "IC22") (pin "3") (pinfunction "1Y_3") (pintype "output"))
    )
    (net (code "237") (name "/VME_DS2") (class "Default")
      (node (ref "IC22") (pin "6") (pinfunction "2Y_6") (pintype "output"))
    )
    (net (code "238") (name "/VME_DTACK") (class "Default")
      (node (ref "IC26") (pin "2") (pinfunction "1A_2") (pintype "input"))
    )
    (net (code "239") (name "/VME_DTACK_OE") (class "Default")
      (node (ref "IC26") (pin "48") (pinfunction "1OEAB_48") (pintype "input"))
    )
    (net (code "241") (name "/VME_D_DIR") (class "Default")
      (node (ref "IC25") (pin "24") (pinfunction "DIR_24") (pintype "input"))
      (node (ref "IC35") (pin "24") (pinfunction "DIR_24") (pintype "input"))
      (node (ref "IC42") (pin "24") (pinfunction "DIR_24") (pintype "input"))
      (node (ref "IC5") (pin "24") (pinfunction "DIR_24") (pintype "input"))
    )
    (net (code "242") (name "/VME_D_OEN") (class "Default")
      (node (ref "IC25") (pin "14") (pinfunction "~{OE}_14") (pintype "input"))
      (node (ref "IC35") (pin "14") (pinfunction "~{OE}_14") (pintype "input"))
      (node (ref "IC42") (pin "14") (pinfunction "~{OE}_14") (pintype "input"))
      (node (ref "IC5") (pin "14") (pinfunction "~{OE}_14") (pintype "input"))
      (node (ref "R175") (pin "1") (pinfunction "1_1") (pintype "passive"))
    )
    (net (code "243") (name "/VME_GA0") (class "Default")
      (node (ref "IC27") (pin "12") (pinfunction "3A2_12") (pintype "bidirectional"))
    )
    (net (code "244") (name "/VME_GA1") (class "Default")
      (node (ref "IC27") (pin "13") (pinfunction "3A3_13") (pintype "bidirectional"))
    )
    (net (code "245") (name "/VME_GA2") (class "Default")
      (node (ref "IC27") (pin "16") (pinfunction "3A4_16") (pintype "bidirectional"))
    )
    (net (code "246") (name "/VME_GA3") (class "Default")
      (node (ref "IC27") (pin "19") (pinfunction "3A5_19") (pintype "bidirectional"))
    )
    (net (code "247") (name "/VME_GA4") (class "Default")
      (node (ref "IC27") (pin "20") (pinfunction "3A6_20") (pintype "bidirectional"))
    )
    (net (code "248") (name "/VME_GAP") (class "Default")
      (node (ref "IC27") (pin "9") (pinfunction "3A1_9") (pintype "bidirectional"))
    )
    (net (code "250") (name "/VME_IACK") (class "Default")
      (node (ref "IC25") (pin "6") (pinfunction "2Y_6") (pintype "output"))
    )
    (net (code "251") (name "/VME_IACKIN") (class "Default")
      (node (ref "IC33") (pin "3") (pinfunction "1Y_3") (pintype "output"))
      (node (ref "R209") (pin "2") (pinfunction "2_2") (pintype "passive"))
    )
    (net (code "252") (name "/VME_IACKOUT") (class "Default")
      (node (ref "IC33") (pin "5") (pinfunction "2A_5") (pintype "input"))
      (node (ref "R209") (pin "1") (pinfunction "1_1") (pintype "passive"))
    )
    (net (code "253") (name "/VME_IRQ1") (class "Default")
      (node (ref "IC25") (pin "48") (pinfunction "1OEAB_48") (pintype "input"))
      (node (ref "R174") (pin "1") (pinfunction "1_1") (pintype "passive"))
    )
    (net (code "254") (name "/VME_IRQ2") (class "Default")
      (node (ref "IC5") (pin "41") (pinfunction "2OEAB_41") (pintype "input"))
      (node (ref "R191") (pin "1") (pinfunction "1_1") (pintype "passive"))
    )
    (net (code "255") (name "/VME_IRQ3") (class "Default")
      (node (ref "IC5") (pin "48") (pinfunction "1OEAB_48") (pintype "input"))
      (node (ref "R190") (pin "1") (pinfunction "1_1") (pintype "passive"))
    )
    (net (code "256") (name "/VME_IRQ4") (class "Default")
      (node (ref "IC42") (pin "41") (pinfunction "2OEAB_41") (pintype "input"))
      (node (ref "R185") (pin "1") (pinfunction "1_1") (pintype "passive"))
    )
    (net (code "257") (name "/VME_IRQ5") (class "Default")
      (node (ref "IC42") (pin "48") (pinfunction "1OEAB_48") (pintype "input"))
      (node (ref "R179") (pin "1") (pinfunction "1_1") (pintype "passive"))
    )
    (net (code "258") (name "/VME_IRQ6") (class "Default")
      (node (ref "IC35") (pin "41") (pinfunction "2OEAB_41") (pintype "input"))
      (node (ref "R177") (pin "1") (pinfunction "1_1") (pintype "passive"))
    )
    (net (code "259") (name "/VME_IRQ7") (class "Default")
      (node (ref "IC35") (pin "48") (pinfunction "1OEAB_48") (pintype "input"))
      (node (ref "R176") (pin "1") (pinfunction "1_1") (pintype "passive"))
    )
    (net (code "261") (name "/VME_LWORD") (class "Default")
      (node (ref "IC22") (pin "23") (pinfunction "3A8_23") (pintype "bidirectional"))
    )
    (net (code "262") (name "/VME_RETRY") (class "Default")
      (node (ref "IC15") (pin "2") (pinfunction "1A_2") (pintype "input"))
    )
    (net (code "263") (name "/VME_RETRY_OE") (class "Default")
      (node (ref "IC15") (pin "48") (pinfunction "1OEAB_48") (pintype "input"))
      (node (ref "R210") (pin "2") (pinfunction "2_2") (pintype "passive"))
    )
    (net (code "264") (name "/VME_SYSCLK") (class "Default")
      (node (ref "IC21") (pin "3") (pinfunction "1Y_3") (pintype "output"))
    )
    (net (code "265") (name "/VME_SYSRESET") (class "Default")
      (node (ref "IC15") (pin "22") (pinfunction "3A7_22") (pintype "bidirectional"))
    )
    (net (code "266") (name "/VME_TCK") (class "Default")
      (node (ref "IC15") (pin "23") (pinfunction "3A8_23") (pintype "bidirectional"))
    )
    (net (code "267") (name "/VME_TDI") (class "Default")
      (node (ref "IC27") (pin "22") (pinfunction "3A7_22") (pintype "bidirectional"))
    )
    (net (code "268") (name "/VME_TDO") (class "Default")
      (node (ref "IC27") (pin "5") (pinfunction "2A_5") (pintype "input"))
    )
    (net (code "269") (name "/VME_TDO_OE") (class "Default")
      (node (ref "IC27") (pin "41") (pinfunction "2OEAB_41") (pintype "input"))
    )
    (net (code "270") (name "/VME_TMS") (class "Default")
      (node (ref "IC27") (pin "23") (pinfunction "3A8_23") (pintype "bidirectional"))
    )
    (net (code "271") (name "/VME_TRST") (class "Default")
      (node (ref "IC27") (pin "3") (pinfunction "1Y_3") (pintype "output"))
    )
    (net (code "272") (name "/VME_WRITE") (class "Default")
      (node (ref "IC26") (pin "6") (pinfunction "2Y_6") (pintype "output"))
    )
    (net (code "273") (name "GND") (class "Default")
      (node (ref "C125") (pin "2") (pinfunction "2_2") (pintype "passive"))
      (node (ref "C127") (pin "2") (pinfunction "2_2") (pintype "passive"))
      (node (ref "C132") (pin "2") (pinfunction "2_2") (pintype "passive"))
      (node (ref "C153") (pin "2") (pinfunction "2_2") (pintype "passive"))
      (node (ref "C154") (pin "1") (pinfunction "1_1") (pintype "passive"))
      (node (ref "C164") (pin "2") (pinfunction "2_2") (pintype "passive"))
      (node (ref "C184") (pin "1") (pinfunction "1_1") (pintype "passive"))
      (node (ref "C185") (pin "2") (pinfunction "2_2") (pintype "passive"))
      (node (ref "C226") (pin "1") (pinfunction "1_1") (pintype "passive"))
      (node (ref "C227") (pin "1") (pinfunction "1_1") (pintype "passive"))
      (node (ref "C240") (pin "2") (pinfunction "2_2") (pintype "passive"))
      (node (ref "C244") (pin "1") (pinfunction "1_1") (pintype "passive"))
      (node (ref "C245") (pin "1") (pinfunction "1_1") (pintype "passive"))
      (node (ref "C246") (pin "1") (pinfunction "1_1") (pintype "passive"))
      (node (ref "C247") (pin "2") (pinfunction "2_2") (pintype "passive"))
      (node (ref "C248") (pin "2") (pinfunction "2_2") (pintype "passive"))
      (node (ref "C249") (pin "2") (pinfunction "2_2") (pintype "passive"))
      (node (ref "C250") (pin "1") (pinfunction "1_1") (pintype "passive"))
      (node (ref "C251") (pin "1") (pinfunction "1_1") (pintype "passive"))
      (node (ref "C252") (pin "1") (pinfunction "1_1") (pintype "passive"))
      (node (ref "C253") (pin "2") (pinfunction "2_2") (pintype "passive"))
      (node (ref "C254") (pin "1") (pinfunction "1_1") (pintype "passive"))
      (node (ref "C257") (pin "1") (pinfunction "1_1") (pintype "passive"))
      (node (ref "C264") (pin "2") (pinfunction "2_2") (pintype "passive"))
      (node (ref "C287") (pin "2") (pinfunction "2_2") (pintype "passive"))
      (node (ref "C292") (pin "1") (pinfunction "1_1") (pintype "passive"))
      (node (ref "C293") (pin "1") (pinfunction "1_1") (pintype "passive"))
      (node (ref "C294") (pin "2") (pinfunction "2_2") (pintype "passive"))
      (node (ref "C295") (pin "1") (pinfunction "1_1") (pintype "passive"))
      (node (ref "C296") (pin "2") (pinfunction "2_2") (pintype "passive"))
      (node (ref "C318") (pin "1") (pinfunction "1_1") (pintype "passive"))
      (node (ref "C319") (pin "2") (pinfunction "2_2") (pintype "passive"))
      (node (ref "C326") (pin "2") (pinfunction "2_2") (pintype "passive"))
      (node (ref "C327") (pin "1") (pinfunction "1_1") (pintype "passive"))
      (node (ref "C328") (pin "2") (pinfunction "2_2") (pintype "passive"))
      (node (ref "C329") (pin "1") (pinfunction "1_1") (pintype "passive"))
      (node (ref "C331") (pin "2") (pinfunction "2_2") (pintype "passive"))
      (node (ref "C332") (pin "1") (pinfunction "1_1") (pintype "passive"))
      (node (ref "C335") (pin "1") (pinfunction "1_1") (pintype "passive"))
      (node (ref "C336") (pin "2") (pinfunction "2_2") (pintype "passive"))
      (node (ref "C337") (pin "1") (pinfunction "1_1") (pintype "passive"))
      (node (ref "C338") (pin "2") (pinfunction "2_2") (pintype "passive"))
      (node (ref "C436") (pin "2") (pinfunction "2_2") (pintype "passive"))
      (node (ref "C437") (pin "1") (pinfunction "1_1") (pintype "passive"))
      (node (ref "C447") (pin "2") (pinfunction "2_2") (pintype "passive"))
      (node (ref "C457") (pin "1") (pinfunction "1_1") (pintype "passive"))
      (node (ref "C464") (pin "2") (pinfunction "2_2") (pintype "passive"))
      (node (ref "C465") (pin "1") (pinfunction "1_1") (pintype "passive"))
      (node (ref "C500") (pin "1") (pinfunction "1_1") (pintype "passive"))
      (node (ref "C501") (pin "2") (pinfunction "2_2") (pintype "passive"))
      (node (ref "C506") (pin "1") (pinfunction "1_1") (pintype "passive"))
      (node (ref "C507") (pin "2") (pinfunction "2_2") (pintype "passive"))
      (node (ref "C512") (pin "1") (pinfunction "1_1") (pintype "passive"))
      (node (ref "C513") (pin "2") (pinfunction "2_2") (pintype "passive"))
      (node (ref "C516") (pin "1") (pinfunction "1_1") (pintype "passive"))
      (node (ref "C517") (pin "2") (pinfunction "2_2") (pintype "passive"))
      (node (ref "C519") (pin "2") (pinfunction "2_2") (pintype "passive"))
      (node (ref "C520") (pin "1") (pinfunction "1_1") (pintype "passive"))
      (node (ref "C521") (pin "2") (pinfunction "2_2") (pintype "passive"))
      (node (ref "C522") (pin "1") (pinfunction "1_1") (pintype "passive"))
      (node (ref "IC15") (pin "10") (pinfunction "GND_10") (pintype "power_in"))
      (node (ref "IC15") (pin "14") (pinfunction "~{OE}_14") (pintype "input"))
      (node (ref "IC15") (pin "15") (pinfunction "GND_15") (pintype "power_in"))
      (node (ref "IC15") (pin "17") (pinfunction "CLKBA_17") (pintype "input"))
      (node (ref "IC15") (pin "21") (pinfunction "GND_21") (pintype "power_in"))
      (node (ref "IC15") (pin "24") (pinfunction "DIR_24") (pintype "input"))
      (node (ref "IC15") (pin "28") (pinfunction "GND_28") (pintype "power_in"))
      (node (ref "IC15") (pin "32") (pinfunction "CLKAB_32") (pintype "input"))
      (node (ref "IC15") (pin "34") (pinfunction "GND_34") (pintype "power_in"))
      (node (ref "IC15") (pin "39") (pinfunction "GND_39") (pintype "power_in"))
      (node (ref "IC15") (pin "4") (pinfunction "GND_4") (pintype "power_in"))
      (node (ref "IC15") (pin "45") (pinfunction "GND_45") (pintype "input"))
      (node (ref "IC15") (pin "5") (pinfunction "2A_5") (pintype "input"))
      (node (ref "IC21") (pin "1") (pinfunction "~{1OEBY}_1") (pintype "input"))
      (node (ref "IC21") (pin "10") (pinfunction "GND_10") (pintype "power_in"))
      (node (ref "IC21") (pin "15") (pinfunction "GND_15") (pintype "power_in"))
      (node (ref "IC21") (pin "17") (pinfunction "CLKBA_17") (pintype "input"))
      (node (ref "IC21") (pin "2") (pinfunction "1A_2") (pintype "input"))
      (node (ref "IC21") (pin "21") (pinfunction "GND_21") (pintype "power_in"))
      (node (ref "IC21") (pin "28") (pinfunction "GND_28") (pintype "power_in"))
      (node (ref "IC21") (pin "32") (pinfunction "CLKAB_32") (pintype "input"))
      (node (ref "IC21") (pin "34") (pinfunction "GND_34") (pintype "power_in"))
      (node (ref "IC21") (pin "39") (pinfunction "GND_39") (pintype "power_in"))
      (node (ref "IC21") (pin "4") (pinfunction "GND_4") (pintype "power_in"))
      (node (ref "IC21") (pin "41") (pinfunction "2OEAB_41") (pintype "input"))
      (node (ref "IC21") (pin "45") (pinfunction "GND_45") (pintype "input"))
      (node (ref "IC21") (pin "48") (pinfunction "1OEAB_48") (pintype "input"))
      (node (ref "IC21") (pin "5") (pinfunction "2A_5") (pintype "input"))
      (node (ref "IC21") (pin "8") (pinfunction "2~{OEBY}_8") (pintype "input"))
      (node (ref "IC22") (pin "1") (pinfunction "~{1OEBY}_1") (pintype "input"))
      (node (ref "IC22") (pin "10") (pinfunction "GND_10") (pintype "power_in"))
      (node (ref "IC22") (pin "15") (pinfunction "GND_15") (pintype "power_in"))
      (node (ref "IC22") (pin "17") (pinfunction "CLKBA_17") (pintype "input"))
      (node (ref "IC22") (pin "2") (pinfunction "1A_2") (pintype "input"))
      (node (ref "IC22") (pin "21") (pinfunction "GND_21") (pintype "power_in"))
      (node (ref "IC22") (pin "28") (pinfunction "GND_28") (pintype "power_in"))
      (node (ref "IC22") (pin "32") (pinfunction "CLKAB_32") (pintype "input"))
      (node (ref "IC22") (pin "34") (pinfunction "GND_34") (pintype "power_in"))
      (node (ref "IC22") (pin "39") (pinfunction "GND_39") (pintype "power_in"))
      (node (ref "IC22") (pin "4") (pinfunction "GND_4") (pintype "power_in"))
      (node (ref "IC22") (pin "41") (pinfunction "2OEAB_41") (pintype "input"))
      (node (ref "IC22") (pin "45") (pinfunction "GND_45") (pintype "input"))
      (node (ref "IC22") (pin "48") (pinfunction "1OEAB_48") (pintype "input"))
      (node (ref "IC22") (pin "5") (pinfunction "2A_5") (pintype "input"))
      (node (ref "IC22") (pin "8") (pinfunction "2~{OEBY}_8") (pintype "input"))
      (node (ref "IC25") (pin "10") (pinfunction "GND_10") (pintype "power_in"))
      (node (ref "IC25") (pin "15") (pinfunction "GND_15") (pintype "power_in"))
      (node (ref "IC25") (pin "17") (pinfunction "CLKBA_17") (pintype "input"))
      (node (ref "IC25") (pin "2") (pinfunction "1A_2") (pintype "input"))
      (node (ref "IC25") (pin "21") (pinfunction "GND_21") (pintype "power_in"))
      (node (ref "IC25") (pin "28") (pinfunction "GND_28") (pintype "power_in"))
      (node (ref "IC25") (pin "32") (pinfunction "CLKAB_32") (pintype "input"))
      (node (ref "IC25") (pin "34") (pinfunction "GND_34") (pintype "power_in"))
      (node (ref "IC25") (pin "39") (pinfunction "GND_39") (pintype "power_in"))
      (node (ref "IC25") (pin "4") (pinfunction "GND_4") (pintype "power_in"))
      (node (ref "IC25") (pin "41") (pinfunction "2OEAB_41") (pintype "input"))
      (node (ref "IC25") (pin "45") (pinfunction "GND_45") (pintype "input"))
      (node (ref "IC25") (pin "5") (pinfunction "2A_5") (pintype "input"))
      (node (ref "IC25") (pin "8") (pinfunction "2~{OEBY}_8") (pintype "input"))
      (node (ref "IC26") (pin "10") (pinfunction "GND_10") (pintype "power_in"))
      (node (ref "IC26") (pin "15") (pinfunction "GND_15") (pintype "power_in"))
      (node (ref "IC26") (pin "17") (pinfunction "CLKBA_17") (pintype "input"))
      (node (ref "IC26") (pin "21") (pinfunction "GND_21") (pintype "power_in"))
      (node (ref "IC26") (pin "28") (pinfunction "GND_28") (pintype "power_in"))
      (node (ref "IC26") (pin "32") (pinfunction "CLKAB_32") (pintype "input"))
      (node (ref "IC26") (pin "34") (pinfunction "GND_34") (pintype "power_in"))
      (node (ref "IC26") (pin "39") (pinfunction "GND_39") (pintype "power_in"))
      (node (ref "IC26") (pin "4") (pinfunction "GND_4") (pintype "power_in"))
      (node (ref "IC26") (pin "41") (pinfunction "2OEAB_41") (pintype "input"))
      (node (ref "IC26") (pin "45") (pinfunction "GND_45") (pintype "input"))
      (node (ref "IC26") (pin "5") (pinfunction "2A_5") (pintype "input"))
      (node (ref "IC26") (pin "8") (pinfunction "2~{OEBY}_8") (pintype "input"))
      (node (ref "IC27") (pin "1") (pinfunction "~{1OEBY}_1") (pintype "input"))
      (node (ref "IC27") (pin "10") (pinfunction "GND_10") (pintype "power_in"))
      (node (ref "IC27") (pin "14") (pinfunction "~{OE}_14") (pintype "input"))
      (node (ref "IC27") (pin "15") (pinfunction "GND_15") (pintype "power_in"))
      (node (ref "IC27") (pin "17") (pinfunction "CLKBA_17") (pintype "input"))
      (node (ref "IC27") (pin "2") (pinfunction "1A_2") (pintype "input"))
      (node (ref "IC27") (pin "21") (pinfunction "GND_21") (pintype "power_in"))
      (node (ref "IC27") (pin "24") (pinfunction "DIR_24") (pintype "input"))
      (node (ref "IC27") (pin "28") (pinfunction "GND_28") (pintype "power_in"))
      (node (ref "IC27") (pin "32") (pinfunction "CLKAB_32") (pintype "input"))
      (node (ref "IC27") (pin "34") (pinfunction "GND_34") (pintype "power_in"))
      (node (ref "IC27") (pin "39") (pinfunction "GND_39") (pintype "power_in"))
      (node (ref "IC27") (pin "4") (pinfunction "GND_4") (pintype "power_in"))
      (node (ref "IC27") (pin "45") (pinfunction "GND_45") (pintype "input"))
      (node (ref "IC27") (pin "48") (pinfunction "1OEAB_48") (pintype "input"))
      (node (ref "IC33") (pin "1") (pinfunction "~{1OEBY}_1") (pintype "input"))
      (node (ref "IC33") (pin "10") (pinfunction "GND_10") (pintype "power_in"))
      (node (ref "IC33") (pin "15") (pinfunction "GND_15") (pintype "power_in"))
      (node (ref "IC33") (pin "17") (pinfunction "CLKBA_17") (pintype "input"))
      (node (ref "IC33") (pin "2") (pinfunction "1A_2") (pintype "input"))
      (node (ref "IC33") (pin "21") (pinfunction "GND_21") (pintype "power_in"))
      (node (ref "IC33") (pin "28") (pinfunction "GND_28") (pintype "power_in"))
      (node (ref "IC33") (pin "32") (pinfunction "CLKAB_32") (pintype "input"))
      (node (ref "IC33") (pin "34") (pinfunction "GND_34") (pintype "power_in"))
      (node (ref "IC33") (pin "39") (pinfunction "GND_39") (pintype "power_in"))
      (node (ref "IC33") (pin "4") (pinfunction "GND_4") (pintype "power_in"))
      (node (ref "IC33") (pin "45") (pinfunction "GND_45") (pintype "input"))
      (node (ref "IC33") (pin "48") (pinfunction "1OEAB_48") (pintype "input"))
      (node (ref "IC35") (pin "10") (pinfunction "GND_10") (pintype "power_in"))
      (node (ref "IC35") (pin "15") (pinfunction "GND_15") (pintype "power_in"))
      (node (ref "IC35") (pin "17") (pinfunction "CLKBA_17") (pintype "input"))
      (node (ref "IC35") (pin "2") (pinfunction "1A_2") (pintype "input"))
      (node (ref "IC35") (pin "21") (pinfunction "GND_21") (pintype "power_in"))
      (node (ref "IC35") (pin "28") (pinfunction "GND_28") (pintype "power_in"))
      (node (ref "IC35") (pin "32") (pinfunction "CLKAB_32") (pintype "input"))
      (node (ref "IC35") (pin "34") (pinfunction "GND_34") (pintype "power_in"))
      (node (ref "IC35") (pin "39") (pinfunction "GND_39") (pintype "power_in"))
      (node (ref "IC35") (pin "4") (pinfunction "GND_4") (pintype "power_in"))
      (node (ref "IC35") (pin "45") (pinfunction "GND_45") (pintype "input"))
      (node (ref "IC35") (pin "5") (pinfunction "2A_5") (pintype "input"))
      (node (ref "IC42") (pin "10") (pinfunction "GND_10") (pintype "power_in"))
      (node (ref "IC42") (pin "15") (pinfunction "GND_15") (pintype "power_in"))
      (node (ref "IC42") (pin "17") (pinfunction "CLKBA_17") (pintype "input"))
      (node (ref "IC42") (pin "2") (pinfunction "1A_2") (pintype "input"))
      (node (ref "IC42") (pin "21") (pinfunction "GND_21") (pintype "power_in"))
      (node (ref "IC42") (pin "28") (pinfunction "GND_28") (pintype "power_in"))
      (node (ref "IC42") (pin "32") (pinfunction "CLKAB_32") (pintype "input"))
      (node (ref "IC42") (pin "34") (pinfunction "GND_34") (pintype "power_in"))
      (node (ref "IC42") (pin "39") (pinfunction "GND_39") (pintype "power_in"))
      (node (ref "IC42") (pin "4") (pinfunction "GND_4") (pintype "power_in"))
      (node (ref "IC42") (pin "45") (pinfunction "GND_45") (pintype "input"))
      (node (ref "IC42") (pin "5") (pinfunction "2A_5") (pintype "input"))
      (node (ref "IC5") (pin "10") (pinfunction "GND_10") (pintype "power_in"))
      (node (ref "IC5") (pin "15") (pinfunction "GND_15") (pintype "power_in"))
      (node (ref "IC5") (pin "17") (pinfunction "CLKBA_17") (pintype "input"))
      (node (ref "IC5") (pin "2") (pinfunction "1A_2") (pintype "input"))
      (node (ref "IC5") (pin "21") (pinfunction "GND_21") (pintype "power_in"))
      (node (ref "IC5") (pin "28") (pinfunction "GND_28") (pintype "power_in"))
      (node (ref "IC5") (pin "32") (pinfunction "CLKAB_32") (pintype "input"))
      (node (ref "IC5") (pin "34") (pinfunction "GND_34") (pintype "power_in"))
      (node (ref "IC5") (pin "39") (pinfunction "GND_39") (pintype "power_in"))
      (node (ref "IC5") (pin "4") (pinfunction "GND_4") (pintype "power_in"))
      (node (ref "IC5") (pin "45") (pinfunction "GND_45") (pintype "input"))
      (node (ref "IC5") (pin "5") (pinfunction "2A_5") (pintype "input"))
      (node (ref "P1") (pin "MTG1") (pinfunction "MTG1_MTG1") (pintype "passive"))
      (node (ref "P1") (pin "MTG2") (pinfunction "MTG2_MTG2") (pintype "passive"))
      (node (ref "P1") (pin "a11") (pinfunction "a11_a11") (pintype "bidirectional"))
      (node (ref "P1") (pin "a15") (pinfunction "a15_a15") (pintype "bidirectional"))
      (node (ref "P1") (pin "a17") (pinfunction "a17_a17") (pintype "bidirectional"))
      (node (ref "P1") (pin "a19") (pinfunction "a19_a19") (pintype "bidirectional"))
      (node (ref "P1") (pin "a9") (pinfunction "a9_a9") (pintype "bidirectional"))
      (node (ref "P1") (pin "b20") (pinfunction "b20_b20") (pintype "bidirectional"))
      (node (ref "P1") (pin "b23") (pinfunction "b23_b23") (pintype "bidirectional"))
      (node (ref "P1") (pin "c9") (pinfunction "c9_c9") (pintype "bidirectional"))
      (node (ref "P1") (pin "d2") (pinfunction "d2_d2") (pintype "bidirectional"))
      (node (ref "P1") (pin "d31") (pinfunction "d31_d31") (pintype "bidirectional"))
      (node (ref "P1") (pin "z10") (pinfunction "z10_z10") (pintype "bidirectional"))
      (node (ref "P1") (pin "z12") (pinfunction "z12_z12") (pintype "bidirectional"))
      (node (ref "P1") (pin "z14") (pinfunction "z14_z14") (pintype "bidirectional"))
      (node (ref "P1") (pin "z16") (pinfunction "z16_z16") (pintype "bidirectional"))
      (node (ref "P1") (pin "z18") (pinfunction "z18_z18") (pintype "bidirectional"))
      (node (ref "P1") (pin "z2") (pinfunction "z2_z2") (pintype "bidirectional"))
      (node (ref "P1") (pin "z20") (pinfunction "z20_z20") (pintype "bidirectional"))
      (node (ref "P1") (pin "z22") (pinfunction "z22_z22") (pintype "bidirectional"))
      (node (ref "P1") (pin "z24") (pinfunction "z24_z24") (pintype "bidirectional"))
      (node (ref "P1") (pin "z26") (pinfunction "z26_z26") (pintype "bidirectional"))
      (node (ref "P1") (pin "z28") (pinfunction "z28_z28") (pintype "bidirectional"))
      (node (ref "P1") (pin "z30") (pinfunction "z30_z30") (pintype "bidirectional"))
      (node (ref "P1") (pin "z32") (pinfunction "z32_z32") (pintype "bidirectional"))
      (node (ref "P1") (pin "z4") (pinfunction "z4_z4") (pintype "bidirectional"))
      (node (ref "P1") (pin "z6") (pinfunction "z6_z6") (pintype "bidirectional"))
      (node (ref "P1") (pin "z8") (pinfunction "z8_z8") (pintype "bidirectional"))
      (node (ref "P3") (pin "MTG1") (pinfunction "MTG1_MTG1") (pintype "passive"))
      (node (ref "P3") (pin "MTG2") (pinfunction "MTG2_MTG2") (pintype "passive"))
      (node (ref "P3") (pin "a1") (pinfunction "a1_a1") (pintype "bidirectional"))
      (node (ref "P3") (pin "a10") (pinfunction "a10_a10") (pintype "bidirectional"))
      (node (ref "P3") (pin "a13") (pinfunction "a13_a13") (pintype "bidirectional"))
      (node (ref "P3") (pin "a16") (pinfunction "a16_a16") (pintype "bidirectional"))
      (node (ref "P3") (pin "a19") (pinfunction "a19_a19") (pintype "bidirectional"))
      (node (ref "P3") (pin "a22") (pinfunction "a22_a22") (pintype "bidirectional"))
      (node (ref "P3") (pin "a25") (pinfunction "a25_a25") (pintype "bidirectional"))
      (node (ref "P3") (pin "a28") (pinfunction "a28_a28") (pintype "bidirectional"))
      (node (ref "P3") (pin "a31") (pinfunction "a31_a31") (pintype "bidirectional"))
      (node (ref "P3") (pin "a32") (pinfunction "a32_a32") (pintype "bidirectional"))
      (node (ref "P3") (pin "a4") (pinfunction "a4_a4") (pintype "bidirectional"))
      (node (ref "P3") (pin "a7") (pinfunction "a7_a7") (pintype "bidirectional"))
      (node (ref "P3") (pin "b12") (pinfunction "b12_b12") (pintype "bidirectional"))
      (node (ref "P3") (pin "b2") (pinfunction "b2_b2") (pintype "bidirectional"))
      (node (ref "P3") (pin "b22") (pinfunction "b22_b22") (pintype "bidirectional"))
      (node (ref "P3") (pin "b31") (pinfunction "b31_b31") (pintype "bidirectional"))
      (node (ref "P3") (pin "c23") (pinfunction "c23_c23") (pintype "bidirectional"))
      (node (ref "P3") (pin "c24") (pinfunction "c24_c24") (pintype "bidirectional"))
      (node (ref "P3") (pin "c27") (pinfunction "c27_c27") (pintype "bidirectional"))
      (node (ref "P3") (pin "c28") (pinfunction "c28_c28") (pintype "bidirectional"))
      (node (ref "P3") (pin "c31") (pinfunction "c31_c31") (pintype "bidirectional"))
      (node (ref "P3") (pin "c32") (pinfunction "c32_c32") (pintype "bidirectional"))
      (node (ref "P3") (pin "d1") (pinfunction "d1_d1") (pintype "bidirectional"))
      (node (ref "P3") (pin "d10") (pinfunction "d10_d10") (pintype "bidirectional"))
      (node (ref "P3") (pin "d13") (pinfunction "d13_d13") (pintype "bidirectional"))
      (node (ref "P3") (pin "d16") (pinfunction "d16_d16") (pintype "bidirectional"))
      (node (ref "P3") (pin "d19") (pinfunction "d19_d19") (pintype "bidirectional"))
      (node (ref "P3") (pin "d22") (pinfunction "d22_d22") (pintype "bidirectional"))
      (node (ref "P3") (pin "d25") (pinfunction "d25_d25") (pintype "bidirectional"))
      (node (ref "P3") (pin "d28") (pinfunction "d28_d28") (pintype "bidirectional"))
      (node (ref "P3") (pin "d31") (pinfunction "d31_d31") (pintype "bidirectional"))
      (node (ref "P3") (pin "d4") (pinfunction "d4_d4") (pintype "bidirectional"))
      (node (ref "P3") (pin "d7") (pinfunction "d7_d7") (pintype "bidirectional"))
      (node (ref "P3") (pin "z10") (pinfunction "z10_z10") (pintype "bidirectional"))
      (node (ref "P3") (pin "z12") (pinfunction "z12_z12") (pintype "bidirectional"))
      (node (ref "P3") (pin "z14") (pinfunction "z14_z14") (pintype "bidirectional"))
      (node (ref "P3") (pin "z16") (pinfunction "z16_z16") (pintype "bidirectional"))
      (node (ref "P3") (pin "z18") (pinfunction "z18_z18") (pintype "bidirectional"))
      (node (ref "P3") (pin "z2") (pinfunction "z2_z2") (pintype "bidirectional"))
      (node (ref "P3") (pin "z20") (pinfunction "z20_z20") (pintype "bidirectional"))
      (node (ref "P3") (pin "z22") (pinfunction "z22_z22") (pintype "bidirectional"))
      (node (ref "P3") (pin "z24") (pinfunction "z24_z24") (pintype "bidirectional"))
      (node (ref "P3") (pin "z26") (pinfunction "z26_z26") (pintype "bidirectional"))
      (node (ref "P3") (pin "z28") (pinfunction "z28_z28") (pintype "bidirectional"))
      (node (ref "P3") (pin "z30") (pinfunction "z30_z30") (pintype "bidirectional"))
      (node (ref "P3") (pin "z32") (pinfunction "z32_z32") (pintype "bidirectional"))
      (node (ref "P3") (pin "z4") (pinfunction "z4_z4") (pintype "bidirectional"))
      (node (ref "P3") (pin "z6") (pinfunction "z6_z6") (pintype "bidirectional"))
      (node (ref "P3") (pin "z8") (pinfunction "z8_z8") (pintype "bidirectional"))
      (node (ref "R174") (pin "2") (pinfunction "2_2") (pintype "passive"))
      (node (ref "R176") (pin "2") (pinfunction "2_2") (pintype "passive"))
      (node (ref "R177") (pin "2") (pinfunction "2_2") (pintype "passive"))
      (node (ref "R179") (pin "2") (pinfunction "2_2") (pintype "passive"))
      (node (ref "R185") (pin "2") (pinfunction "2_2") (pintype "passive"))
      (node (ref "R190") (pin "2") (pinfunction "2_2") (pintype "passive"))
      (node (ref "R191") (pin "2") (pinfunction "2_2") (pintype "passive"))
      (node (ref "R210") (pin "1") (pinfunction "1_1") (pintype "passive"))
      (node (ref "R211") (pin "1") (pinfunction "1_1") (pintype "passive"))
    )
    (net (code "274") (name "P3V3") (class "Default")
      (node (ref "C125") (pin "1") (pinfunction "1_1") (pintype "passive"))
      (node (ref "C127") (pin "1") (pinfunction "1_1") (pintype "passive"))
      (node (ref "C132") (pin "1") (pinfunction "1_1") (pintype "passive"))
      (node (ref "C153") (pin "1") (pinfunction "1_1") (pintype "passive"))
      (node (ref "C154") (pin "2") (pinfunction "2_2") (pintype "passive"))
      (node (ref "C164") (pin "1") (pinfunction "1_1") (pintype "passive"))
      (node (ref "C184") (pin "2") (pinfunction "2_2") (pintype "passive"))
      (node (ref "C185") (pin "1") (pinfunction "1_1") (pintype "passive"))
      (node (ref "C226") (pin "2") (pinfunction "2_2") (pintype "passive"))
      (node (ref "C227") (pin "2") (pinfunction "2_2") (pintype "passive"))
      (node (ref "C240") (pin "1") (pinfunction "1_1") (pintype "passive"))
      (node (ref "C244") (pin "2") (pinfunction "2_2") (pintype "passive"))
      (node (ref "C245") (pin "2") (pinfunction "2_2") (pintype "passive"))
      (node (ref "C246") (pin "2") (pinfunction "2_2") (pintype "passive"))
      (node (ref "C247") (pin "1") (pinfunction "1_1") (pintype "passive"))
      (node (ref "C248") (pin "1") (pinfunction "1_1") (pintype "passive"))
      (node (ref "C249") (pin "1") (pinfunction "1_1") (pintype "passive"))
      (node (ref "C250") (pin "2") (pinfunction "2_2") (pintype "passive"))
      (node (ref "C251") (pin "2") (pinfunction "2_2") (pintype "passive"))
      (node (ref "C252") (pin "2") (pinfunction "2_2") (pintype "passive"))
      (node (ref "C253") (pin "1") (pinfunction "1_1") (pintype "passive"))
      (node (ref "C254") (pin "2") (pinfunction "2_2") (pintype "passive"))
      (node (ref "C257") (pin "2") (pinfunction "2_2") (pintype "passive"))
      (node (ref "C264") (pin "1") (pinfunction "1_1") (pintype "passive"))
      (node (ref "C287") (pin "1") (pinfunction "1_1") (pintype "passive"))
      (node (ref "C292") (pin "2") (pinfunction "2_2") (pintype "passive"))
      (node (ref "C293") (pin "2") (pinfunction "2_2") (pintype "passive"))
      (node (ref "C294") (pin "1") (pinfunction "1_1") (pintype "passive"))
      (node (ref "C295") (pin "2") (pinfunction "2_2") (pintype "passive"))
      (node (ref "C296") (pin "1") (pinfunction "1_1") (pintype "passive"))
      (node (ref "C318") (pin "2") (pinfunction "2_2") (pintype "passive"))
      (node (ref "C319") (pin "1") (pinfunction "1_1") (pintype "passive"))
      (node (ref "C326") (pin "1") (pinfunction "1_1") (pintype "passive"))
      (node (ref "C327") (pin "2") (pinfunction "2_2") (pintype "passive"))
      (node (ref "C328") (pin "1") (pinfunction "1_1") (pintype "passive"))
      (node (ref "C329") (pin "2") (pinfunction "2_2") (pintype "passive"))
      (node (ref "C331") (pin "1") (pinfunction "1_1") (pintype "passive"))
      (node (ref "C332") (pin "2") (pinfunction "2_2") (pintype "passive"))
      (node (ref "C335") (pin "2") (pinfunction "2_2") (pintype "passive"))
      (node (ref "C336") (pin "1") (pinfunction "1_1") (pintype "passive"))
      (node (ref "C337") (pin "2") (pinfunction "2_2") (pintype "passive"))
      (node (ref "C338") (pin "1") (pinfunction "1_1") (pintype "passive"))
      (node (ref "C436") (pin "1") (pinfunction "1_1") (pintype "passive"))
      (node (ref "C437") (pin "2") (pinfunction "2_2") (pintype "passive"))
      (node (ref "C447") (pin "1") (pinfunction "1_1") (pintype "passive"))
      (node (ref "C457") (pin "2") (pinfunction "2_2") (pintype "passive"))
      (node (ref "C464") (pin "1") (pinfunction "1_1") (pintype "passive"))
      (node (ref "C465") (pin "2") (pinfunction "2_2") (pintype "passive"))
      (node (ref "C500") (pin "2") (pinfunction "2_2") (pintype "passive"))
      (node (ref "C501") (pin "1") (pinfunction "1_1") (pintype "passive"))
      (node (ref "C506") (pin "2") (pinfunction "2_2") (pintype "passive"))
      (node (ref "C507") (pin "1") (pinfunction "1_1") (pintype "passive"))
      (node (ref "C512") (pin "2") (pinfunction "2_2") (pintype "passive"))
      (node (ref "C513") (pin "1") (pinfunction "1_1") (pintype "passive"))
      (node (ref "C516") (pin "2") (pinfunction "2_2") (pintype "passive"))
      (node (ref "C517") (pin "1") (pinfunction "1_1") (pintype "passive"))
      (node (ref "C519") (pin "1") (pinfunction "1_1") (pintype "passive"))
      (node (ref "C520") (pin "2") (pinfunction "2_2") (pintype "passive"))
      (node (ref "C521") (pin "1") (pinfunction "1_1") (pintype "passive"))
      (node (ref "C522") (pin "2") (pinfunction "2_2") (pintype "passive"))
      (node (ref "IC15") (pin "1") (pinfunction "~{1OEBY}_1") (pintype "input"))
      (node (ref "IC15") (pin "11") (pinfunction "LE_11") (pintype "input"))
      (node (ref "IC15") (pin "18") (pinfunction "VCC_18") (pintype "power_in"))
      (node (ref "IC15") (pin "25") (pinfunction "VCC_25") (pintype "power_in"))
      (node (ref "IC15") (pin "31") (pinfunction "VCC_31") (pintype "power_in"))
      (node (ref "IC15") (pin "35") (pinfunction "VCC_35") (pintype "power_in"))
      (node (ref "IC15") (pin "38") (pinfunction "VCC_38") (pintype "power_in"))
      (node (ref "IC15") (pin "42") (pinfunction "VCC_42") (pintype "power_in"))
      (node (ref "IC15") (pin "44") (pinfunction "BIASVCC_44") (pintype "input"))
      (node (ref "IC15") (pin "47") (pinfunction "VCC_47") (pintype "input"))
      (node (ref "IC15") (pin "7") (pinfunction "VCC_7") (pintype "power_in"))
      (node (ref "IC15") (pin "8") (pinfunction "2~{OEBY}_8") (pintype "input"))
      (node (ref "IC21") (pin "11") (pinfunction "LE_11") (pintype "input"))
      (node (ref "IC21") (pin "18") (pinfunction "VCC_18") (pintype "power_in"))
      (node (ref "IC21") (pin "25") (pinfunction "VCC_25") (pintype "power_in"))
      (node (ref "IC21") (pin "31") (pinfunction "VCC_31") (pintype "power_in"))
      (node (ref "IC21") (pin "35") (pinfunction "VCC_35") (pintype "power_in"))
      (node (ref "IC21") (pin "38") (pinfunction "VCC_38") (pintype "power_in"))
      (node (ref "IC21") (pin "42") (pinfunction "VCC_42") (pintype "power_in"))
      (node (ref "IC21") (pin "44") (pinfunction "BIASVCC_44") (pintype "input"))
      (node (ref "IC21") (pin "47") (pinfunction "VCC_47") (pintype "input"))
      (node (ref "IC21") (pin "7") (pinfunction "VCC_7") (pintype "power_in"))
      (node (ref "IC22") (pin "11") (pinfunction "LE_11") (pintype "input"))
      (node (ref "IC22") (pin "18") (pinfunction "VCC_18") (pintype "power_in"))
      (node (ref "IC22") (pin "25") (pinfunction "VCC_25") (pintype "power_in"))
      (node (ref "IC22") (pin "31") (pinfunction "VCC_31") (pintype "power_in"))
      (node (ref "IC22") (pin "35") (pinfunction "VCC_35") (pintype "power_in"))
      (node (ref "IC22") (pin "38") (pinfunction "VCC_38") (pintype "power_in"))
      (node (ref "IC22") (pin "42") (pinfunction "VCC_42") (pintype "power_in"))
      (node (ref "IC22") (pin "44") (pinfunction "BIASVCC_44") (pintype "input"))
      (node (ref "IC22") (pin "47") (pinfunction "VCC_47") (pintype "input"))
      (node (ref "IC22") (pin "7") (pinfunction "VCC_7") (pintype "power_in"))
      (node (ref "IC25") (pin "1") (pinfunction "~{1OEBY}_1") (pintype "input"))
      (node (ref "IC25") (pin "11") (pinfunction "LE_11") (pintype "input"))
      (node (ref "IC25") (pin "18") (pinfunction "VCC_18") (pintype "power_in"))
      (node (ref "IC25") (pin "25") (pinfunction "VCC_25") (pintype "power_in"))
      (node (ref "IC25") (pin "31") (pinfunction "VCC_31") (pintype "power_in"))
      (node (ref "IC25") (pin "35") (pinfunction "VCC_35") (pintype "power_in"))
      (node (ref "IC25") (pin "38") (pinfunction "VCC_38") (pintype "power_in"))
      (node (ref "IC25") (pin "42") (pinfunction "VCC_42") (pintype "power_in"))
      (node (ref "IC25") (pin "44") (pinfunction "BIASVCC_44") (pintype "input"))
      (node (ref "IC25") (pin "47") (pinfunction "VCC_47") (pintype "input"))
      (node (ref "IC25") (pin "7") (pinfunction "VCC_7") (pintype "power_in"))
      (node (ref "IC26") (pin "1") (pinfunction "~{1OEBY}_1") (pintype "input"))
      (node (ref "IC26") (pin "11") (pinfunction "LE_11") (pintype "input"))
      (node (ref "IC26") (pin "18") (pinfunction "VCC_18") (pintype "power_in"))
      (node (ref "IC26") (pin "25") (pinfunction "VCC_25") (pintype "power_in"))
      (node (ref "IC26") (pin "31") (pinfunction "VCC_31") (pintype "power_in"))
      (node (ref "IC26") (pin "35") (pinfunction "VCC_35") (pintype "power_in"))
      (node (ref "IC26") (pin "38") (pinfunction "VCC_38") (pintype "power_in"))
      (node (ref "IC26") (pin "42") (pinfunction "VCC_42") (pintype "power_in"))
      (node (ref "IC26") (pin "44") (pinfunction "BIASVCC_44") (pintype "input"))
      (node (ref "IC26") (pin "47") (pinfunction "VCC_47") (pintype "input"))
      (node (ref "IC26") (pin "7") (pinfunction "VCC_7") (pintype "power_in"))
      (node (ref "IC27") (pin "11") (pinfunction "LE_11") (pintype "input"))
      (node (ref "IC27") (pin "18") (pinfunction "VCC_18") (pintype "power_in"))
      (node (ref "IC27") (pin "25") (pinfunction "VCC_25") (pintype "power_in"))
      (node (ref "IC27") (pin "31") (pinfunction "VCC_31") (pintype "power_in"))
      (node (ref "IC27") (pin "35") (pinfunction "VCC_35") (pintype "power_in"))
      (node (ref "IC27") (pin "38") (pinfunction "VCC_38") (pintype "power_in"))
      (node (ref "IC27") (pin "42") (pinfunction "VCC_42") (pintype "power_in"))
      (node (ref "IC27") (pin "44") (pinfunction "BIASVCC_44") (pintype "input"))
      (node (ref "IC27") (pin "47") (pinfunction "VCC_47") (pintype "input"))
      (node (ref "IC27") (pin "7") (pinfunction "VCC_7") (pintype "power_in"))
      (node (ref "IC27") (pin "8") (pinfunction "2~{OEBY}_8") (pintype "input"))
      (node (ref "IC33") (pin "11") (pinfunction "LE_11") (pintype "input"))
      (node (ref "IC33") (pin "18") (pinfunction "VCC_18") (pintype "power_in"))
      (node (ref "IC33") (pin "25") (pinfunction "VCC_25") (pintype "power_in"))
      (node (ref "IC33") (pin "31") (pinfunction "VCC_31") (pintype "power_in"))
      (node (ref "IC33") (pin "35") (pinfunction "VCC_35") (pintype "power_in"))
      (node (ref "IC33") (pin "38") (pinfunction "VCC_38") (pintype "power_in"))
      (node (ref "IC33") (pin "41") (pinfunction "2OEAB_41") (pintype "input"))
      (node (ref "IC33") (pin "42") (pinfunction "VCC_42") (pintype "power_in"))
      (node (ref "IC33") (pin "44") (pinfunction "BIASVCC_44") (pintype "input"))
      (node (ref "IC33") (pin "47") (pinfunction "VCC_47") (pintype "input"))
      (node (ref "IC33") (pin "7") (pinfunction "VCC_7") (pintype "power_in"))
      (node (ref "IC33") (pin "8") (pinfunction "2~{OEBY}_8") (pintype "input"))
      (node (ref "IC35") (pin "1") (pinfunction "~{1OEBY}_1") (pintype "input"))
      (node (ref "IC35") (pin "11") (pinfunction "LE_11") (pintype "input"))
      (node (ref "IC35") (pin "18") (pinfunction "VCC_18") (pintype "power_in"))
      (node (ref "IC35") (pin "25") (pinfunction "VCC_25") (pintype "power_in"))
      (node (ref "IC35") (pin "31") (pinfunction "VCC_31") (pintype "power_in"))
      (node (ref "IC35") (pin "35") (pinfunction "VCC_35") (pintype "power_in"))
      (node (ref "IC35") (pin "38") (pinfunction "VCC_38") (pintype "power_in"))
      (node (ref "IC35") (pin "42") (pinfunction "VCC_42") (pintype "power_in"))
      (node (ref "IC35") (pin "44") (pinfunction "BIASVCC_44") (pintype "input"))
      (node (ref "IC35") (pin "47") (pinfunction "VCC_47") (pintype "input"))
      (node (ref "IC35") (pin "7") (pinfunction "VCC_7") (pintype "power_in"))
      (node (ref "IC35") (pin "8") (pinfunction "2~{OEBY}_8") (pintype "input"))
      (node (ref "IC42") (pin "1") (pinfunction "~{1OEBY}_1") (pintype "input"))
      (node (ref "IC42") (pin "11") (pinfunction "LE_11") (pintype "input"))
      (node (ref "IC42") (pin "18") (pinfunction "VCC_18") (pintype "power_in"))
      (node (ref "IC42") (pin "25") (pinfunction "VCC_25") (pintype "power_in"))
      (node (ref "IC42") (pin "31") (pinfunction "VCC_31") (pintype "power_in"))
      (node (ref "IC42") (pin "35") (pinfunction "VCC_35") (pintype "power_in"))
      (node (ref "IC42") (pin "38") (pinfunction "VCC_38") (pintype "power_in"))
      (node (ref "IC42") (pin "42") (pinfunction "VCC_42") (pintype "power_in"))
      (node (ref "IC42") (pin "44") (pinfunction "BIASVCC_44") (pintype "input"))
      (node (ref "IC42") (pin "47") (pinfunction "VCC_47") (pintype "input"))
      (node (ref "IC42") (pin "7") (pinfunction "VCC_7") (pintype "power_in"))
      (node (ref "IC42") (pin "8") (pinfunction "2~{OEBY}_8") (pintype "input"))
      (node (ref "IC5") (pin "1") (pinfunction "~{1OEBY}_1") (pintype "input"))
      (node (ref "IC5") (pin "11") (pinfunction "LE_11") (pintype "input"))
      (node (ref "IC5") (pin "18") (pinfunction "VCC_18") (pintype "power_in"))
      (node (ref "IC5") (pin "25") (pinfunction "VCC_25") (pintype "power_in"))
      (node (ref "IC5") (pin "31") (pinfunction "VCC_31") (pintype "power_in"))
      (node (ref "IC5") (pin "35") (pinfunction "VCC_35") (pintype "power_in"))
      (node (ref "IC5") (pin "38") (pinfunction "VCC_38") (pintype "power_in"))
      (node (ref "IC5") (pin "42") (pinfunction "VCC_42") (pintype "power_in"))
      (node (ref "IC5") (pin "44") (pinfunction "BIASVCC_44") (pintype "input"))
      (node (ref "IC5") (pin "47") (pinfunction "VCC_47") (pintype "input"))
      (node (ref "IC5") (pin "7") (pinfunction "VCC_7") (pintype "power_in"))
      (node (ref "IC5") (pin "8") (pinfunction "2~{OEBY}_8") (pintype "input"))
      (node (ref "P1") (pin "d12") (pinfunction "d12_d12") (pintype "bidirectional"))
      (node (ref "P1") (pin "d14") (pinfunction "d14_d14") (pintype "bidirectional"))
      (node (ref "P1") (pin "d16") (pinfunction "d16_d16") (pintype "bidirectional"))
      (node (ref "P1") (pin "d18") (pinfunction "d18_d18") (pintype "bidirectional"))
      (node (ref "P1") (pin "d20") (pinfunction "d20_d20") (pintype "bidirectional"))
      (node (ref "P1") (pin "d22") (pinfunction "d22_d22") (pintype "bidirectional"))
      (node (ref "P1") (pin "d24") (pinfunction "d24_d24") (pintype "bidirectional"))
      (node (ref "P1") (pin "d26") (pinfunction "d26_d26") (pintype "bidirectional"))
      (node (ref "P1") (pin "d28") (pinfunction "d28_d28") (pintype "bidirectional"))
      (node (ref "P1") (pin "d30") (pinfunction "d30_d30") (pintype "bidirectional"))
      (node (ref "R175") (pin "2") (pinfunction "2_2") (pintype "passive"))
      (node (ref "R203") (pin "2") (pinfunction "2_2") (pintype "passive"))
      (node (ref "R213") (pin "2") (pinfunction "2_2") (pintype "passive"))
      (node (ref "R216") (pin "2") (pinfunction "2_2") (pintype "passive"))
      (node (ref "R217") (pin "2") (pinfunction "2_2") (pintype "passive"))
      (node (ref "R223") (pin "2") (pinfunction "2_2") (pintype "passive"))
      (node (ref "R228") (pin "2") (pinfunction "2_2") (pintype "passive"))
      (node (ref "R230") (pin "2") (pinfunction "2_2") (pintype "passive"))
    )
    (net (code "275") (name "RETV2N0BI") (class "Default")
      (node (ref "P3") (pin "c11") (pinfunction "c11_c11") (pintype "bidirectional"))
      (node (ref "P3") (pin "c12") (pinfunction "c12_c12") (pintype "bidirectional"))
    )
    (net (code "276") (name "RETV5N2BI") (class "Default")
      (node (ref "P3") (pin "c15") (pinfunction "c15_c15") (pintype "bidirectional"))
      (node (ref "P3") (pin "c16") (pinfunction "c16_c16") (pintype "bidirectional"))
    )
    (net (code "277") (name "RETV5P0BI") (class "Default")
      (node (ref "P3") (pin "c7") (pinfunction "c7_c7") (pintype "bidirectional"))
      (node (ref "P3") (pin "c8") (pinfunction "c8_c8") (pintype "bidirectional"))
    )
    (net (code "278") (name "RETV15N0BI") (class "Default")
      (node (ref "P3") (pin "c19") (pinfunction "c19_c19") (pintype "bidirectional"))
      (node (ref "P3") (pin "c20") (pinfunction "c20_c20") (pintype "bidirectional"))
    )
    (net (code "279") (name "RETV15P0BI") (class "Default")
      (node (ref "P3") (pin "c3") (pinfunction "c3_c3") (pintype "bidirectional"))
      (node (ref "P3") (pin "c4") (pinfunction "c4_c4") (pintype "bidirectional"))
    )
    (net (code "280") (name "V2N0BI") (class "Default")
      (node (ref "P3") (pin "c10") (pinfunction "c10_c10") (pintype "bidirectional"))
      (node (ref "P3") (pin "c9") (pinfunction "c9_c9") (pintype "bidirectional"))
    )
    (net (code "281") (name "V5N2BI") (class "Default")
      (node (ref "P3") (pin "c13") (pinfunction "c13_c13") (pintype "bidirectional"))
      (node (ref "P3") (pin "c14") (pinfunction "c14_c14") (pintype "bidirectional"))
    )
    (net (code "282") (name "V5P0BI") (class "Default")
      (node (ref "P3") (pin "c5") (pinfunction "c5_c5") (pintype "bidirectional"))
      (node (ref "P3") (pin "c6") (pinfunction "c6_c6") (pintype "bidirectional"))
    )
    (net (code "283") (name "V5P0STDBYVME") (class "Default")
      (node (ref "P1") (pin "b31") (pinfunction "b31_b31") (pintype "bidirectional"))
    )
    (net (code "284") (name "V5P0VME") (class "Default")
      (node (ref "P1") (pin "a32") (pinfunction "a32_a32") (pintype "bidirectional"))
      (node (ref "P1") (pin "b32") (pinfunction "b32_b32") (pintype "bidirectional"))
      (node (ref "P1") (pin "c32") (pinfunction "c32_c32") (pintype "bidirectional"))
      (node (ref "P3") (pin "b1") (pinfunction "b1_b1") (pintype "bidirectional"))
      (node (ref "P3") (pin "b13") (pinfunction "b13_b13") (pintype "bidirectional"))
      (node (ref "P3") (pin "b32") (pinfunction "b32_b32") (pintype "bidirectional"))
    )
    (net (code "285") (name "V12N0VME") (class "Default")
      (node (ref "P1") (pin "a31") (pinfunction "a31_a31") (pintype "bidirectional"))
    )
    (net (code "286") (name "V12P0VME") (class "Default")
      (node (ref "P1") (pin "c31") (pinfunction "c31_c31") (pintype "bidirectional"))
    )
    (net (code "287") (name "V15N0BI") (class "Default")
      (node (ref "P3") (pin "c17") (pinfunction "c17_c17") (pintype "bidirectional"))
      (node (ref "P3") (pin "c18") (pinfunction "c18_c18") (pintype "bidirectional"))
    )
    (net (code "288") (name "V15P0BI") (class "Default")
      (node (ref "P3") (pin "c1") (pinfunction "c1_c1") (pintype "bidirectional"))
      (node (ref "P3") (pin "c2") (pinfunction "c2_c2") (pintype "bidirectional"))
    )
    (net (code "289") (name "unconnected-(IC5-1Y-Pad3)") (class "Default")
      (node (ref "IC5") (pin "3") (pinfunction "1Y_3") (pintype "output+no_connect"))
    )
    (net (code "290") (name "unconnected-(IC5-2Y-Pad6)") (class "Default")
      (node (ref "IC5") (pin "6") (pinfunction "2Y_6") (pintype "output+no_connect"))
    )
    (net (code "291") (name "unconnected-(IC15-1Y-Pad3)") (class "Default")
      (node (ref "IC15") (pin "3") (pinfunction "1Y_3") (pintype "output+no_connect"))
    )
    (net (code "292") (name "unconnected-(IC15-2Y-Pad6)") (class "Default")
      (node (ref "IC15") (pin "6") (pinfunction "2Y_6") (pintype "output+no_connect"))
    )
    (net (code "293") (name "unconnected-(IC25-1Y-Pad3)") (class "Default")
      (node (ref "IC25") (pin "3") (pinfunction "1Y_3") (pintype "output+no_connect"))
    )
    (net (code "294") (name "unconnected-(IC26-1Y-Pad3)") (class "Default")
      (node (ref "IC26") (pin "3") (pinfunction "1Y_3") (pintype "output+no_connect"))
    )
    (net (code "295") (name "unconnected-(IC27-2Y-Pad6)") (class "Default")
      (node (ref "IC27") (pin "6") (pinfunction "2Y_6") (pintype "output+no_connect"))
    )
    (net (code "296") (name "unconnected-(IC33-2Y-Pad6)") (class "Default")
      (node (ref "IC33") (pin "6") (pinfunction "2Y_6") (pintype "output+no_connect"))
    )
    (net (code "297") (name "unconnected-(IC35-1Y-Pad3)") (class "Default")
      (node (ref "IC35") (pin "3") (pinfunction "1Y_3") (pintype "output+no_connect"))
    )
    (net (code "298") (name "unconnected-(IC35-2Y-Pad6)") (class "Default")
      (node (ref "IC35") (pin "6") (pinfunction "2Y_6") (pintype "output+no_connect"))
    )
    (net (code "299") (name "unconnected-(IC42-1Y-Pad3)") (class "Default")
      (node (ref "IC42") (pin "3") (pinfunction "1Y_3") (pintype "output+no_connect"))
    )
    (net (code "300") (name "unconnected-(IC42-2Y-Pad6)") (class "Default")
      (node (ref "IC42") (pin "6") (pinfunction "2Y_6") (pintype "output+no_connect"))
    )
    (net (code "301") (name "unconnected-(P1-Padd1)") (class "Default")
      (node (ref "P1") (pin "d1") (pinfunction "d1_d1") (pintype "bidirectional+no_connect"))
    )
    (net (code "302") (name "unconnected-(P1-Padd3)") (class "Default")
      (node (ref "P1") (pin "d3") (pinfunction "d3_d3") (pintype "bidirectional+no_connect"))
    )
    (net (code "303") (name "unconnected-(P1-Padd4)") (class "Default")
      (node (ref "P1") (pin "d4") (pinfunction "d4_d4") (pintype "bidirectional+no_connect"))
    )
    (net (code "304") (name "unconnected-(P1-Padd5)") (class "Default")
      (node (ref "P1") (pin "d5") (pinfunction "d5_d5") (pintype "bidirectional+no_connect"))
    )
    (net (code "305") (name "unconnected-(P1-Padd6)") (class "Default")
      (node (ref "P1") (pin "d6") (pinfunction "d6_d6") (pintype "bidirectional+no_connect"))
    )
    (net (code "306") (name "unconnected-(P1-Padd7)") (class "Default")
      (node (ref "P1") (pin "d7") (pinfunction "d7_d7") (pintype "bidirectional+no_connect"))
    )
    (net (code "307") (name "unconnected-(P1-Padd8)") (class "Default")
      (node (ref "P1") (pin "d8") (pinfunction "d8_d8") (pintype "bidirectional+no_connect"))
    )
    (net (code "308") (name "unconnected-(P1-Padd19)") (class "Default")
      (node (ref "P1") (pin "d19") (pinfunction "d19_d19") (pintype "bidirectional+no_connect"))
    )
    (net (code "309") (name "unconnected-(P1-Padd21)") (class "Default")
      (node (ref "P1") (pin "d21") (pinfunction "d21_d21") (pintype "bidirectional+no_connect"))
    )
    (net (code "310") (name "unconnected-(P1-Padd23)") (class "Default")
      (node (ref "P1") (pin "d23") (pinfunction "d23_d23") (pintype "bidirectional+no_connect"))
    )
    (net (code "311") (name "unconnected-(P1-Padd25)") (class "Default")
      (node (ref "P1") (pin "d25") (pinfunction "d25_d25") (pintype "bidirectional+no_connect"))
    )
    (net (code "312") (name "unconnected-(P1-Padd27)") (class "Default")
      (node (ref "P1") (pin "d27") (pinfunction "d27_d27") (pintype "bidirectional+no_connect"))
    )
    (net (code "313") (name "unconnected-(P1-Padd29)") (class "Default")
      (node (ref "P1") (pin "d29") (pinfunction "d29_d29") (pintype "bidirectional+no_connect"))
    )
    (net (code "314") (name "unconnected-(P1-Padd32)") (class "Default")
      (node (ref "P1") (pin "d32") (pinfunction "d32_d32") (pintype "bidirectional+no_connect"))
    )
    (net (code "315") (name "unconnected-(P1-Padz11)") (class "Default")
      (node (ref "P1") (pin "z11") (pinfunction "z11_z11") (pintype "bidirectional+no_connect"))
    )
    (net (code "316") (name "unconnected-(P1-Padz13)") (class "Default")
      (node (ref "P1") (pin "z13") (pinfunction "z13_z13") (pintype "bidirectional+no_connect"))
    )
    (net (code "317") (name "unconnected-(P1-Padz15)") (class "Default")
      (node (ref "P1") (pin "z15") (pinfunction "z15_z15") (pintype "bidirectional+no_connect"))
    )
    (net (code "318") (name "unconnected-(P1-Padz17)") (class "Default")
      (node (ref "P1") (pin "z17") (pinfunction "z17_z17") (pintype "bidirectional+no_connect"))
    )
    (net (code "319") (name "unconnected-(P1-Padz19)") (class "Default")
      (node (ref "P1") (pin "z19") (pinfunction "z19_z19") (pintype "bidirectional+no_connect"))
    )
    (net (code "320") (name "unconnected-(P1-Padz21)") (class "Default")
      (node (ref "P1") (pin "z21") (pinfunction "z21_z21") (pintype "bidirectional+no_connect"))
    )
    (net (code "321") (name "unconnected-(P1-Padz23)") (class "Default")
      (node (ref "P1") (pin "z23") (pinfunction "z23_z23") (pintype "bidirectional+no_connect"))
    )
    (net (code "322") (name "unconnected-(P1-Padz25)") (class "Default")
      (node (ref "P1") (pin "z25") (pinfunction "z25_z25") (pintype "bidirectional+no_connect"))
    )
    (net (code "323") (name "unconnected-(P1-Padz27)") (class "Default")
      (node (ref "P1") (pin "z27") (pinfunction "z27_z27") (pintype "bidirectional+no_connect"))
    )
    (net (code "324") (name "unconnected-(P1-Padz29)") (class "Default")
      (node (ref "P1") (pin "z29") (pinfunction "z29_z29") (pintype "bidirectional+no_connect"))
    )
    (net (code "325") (name "unconnected-(P1-Padz31)") (class "Default")
      (node (ref "P1") (pin "z31") (pinfunction "z31_z31") (pintype "bidirectional+no_connect"))
    )
    (net (code "326") (name "unconnected-(P3-Padc21)") (class "Default")
      (node (ref "P3") (pin "c21") (pinfunction "c21_c21") (pintype "bidirectional"))
    )
    (net (code "327") (name "unconnected-(P3-Padc22)") (class "Default")
      (node (ref "P3") (pin "c22") (pinfunction "c22_c22") (pintype "bidirectional"))
    )
    (net (code "328") (name "unconnected-(P3-Padd32)") (class "Default")
      (node (ref "P3") (pin "d32") (pinfunction "d32_d32") (pintype "bidirectional+no_connect"))
    )
    (net (code "329") (name "unconnected-(P3-Padz1)") (class "Default")
      (node (ref "P3") (pin "z1") (pinfunction "z1_z1") (pintype "bidirectional+no_connect"))
    )
    (net (code "330") (name "unconnected-(P3-Padz3)") (class "Default")
      (node (ref "P3") (pin "z3") (pinfunction "z3_z3") (pintype "bidirectional+no_connect"))
    )
    (net (code "331") (name "unconnected-(P3-Padz5)") (class "Default")
      (node (ref "P3") (pin "z5") (pinfunction "z5_z5") (pintype "bidirectional+no_connect"))
    )
    (net (code "332") (name "unconnected-(P3-Padz7)") (class "Default")
      (node (ref "P3") (pin "z7") (pinfunction "z7_z7") (pintype "bidirectional+no_connect"))
    )
    (net (code "333") (name "unconnected-(P3-Padz9)") (class "Default")
      (node (ref "P3") (pin "z9") (pinfunction "z9_z9") (pintype "bidirectional+no_connect"))
    )
    (net (code "334") (name "unconnected-(P3-Padz11)") (class "Default")
      (node (ref "P3") (pin "z11") (pinfunction "z11_z11") (pintype "bidirectional+no_connect"))
    )
    (net (code "335") (name "unconnected-(P3-Padz13)") (class "Default")
      (node (ref "P3") (pin "z13") (pinfunction "z13_z13") (pintype "bidirectional+no_connect"))
    )
    (net (code "336") (name "unconnected-(P3-Padz15)") (class "Default")
      (node (ref "P3") (pin "z15") (pinfunction "z15_z15") (pintype "bidirectional+no_connect"))
    )
    (net (code "337") (name "unconnected-(P3-Padz17)") (class "Default")
      (node (ref "P3") (pin "z17") (pinfunction "z17_z17") (pintype "bidirectional+no_connect"))
    )
    (net (code "338") (name "unconnected-(P3-Padz19)") (class "Default")
      (node (ref "P3") (pin "z19") (pinfunction "z19_z19") (pintype "bidirectional+no_connect"))
    )
    (net (code "339") (name "unconnected-(P3-Padz21)") (class "Default")
      (node (ref "P3") (pin "z21") (pinfunction "z21_z21") (pintype "bidirectional+no_connect"))
    )
    (net (code "340") (name "unconnected-(P3-Padz23)") (class "Default")
      (node (ref "P3") (pin "z23") (pinfunction "z23_z23") (pintype "bidirectional+no_connect"))
    )
    (net (code "341") (name "unconnected-(P3-Padz25)") (class "Default")
      (node (ref "P3") (pin "z25") (pinfunction "z25_z25") (pintype "bidirectional+no_connect"))
    )
    (net (code "342") (name "unconnected-(P3-Padz27)") (class "Default")
      (node (ref "P3") (pin "z27") (pinfunction "z27_z27") (pintype "bidirectional+no_connect"))
    )
    (net (code "343") (name "unconnected-(P3-Padz29)") (class "Default")
      (node (ref "P3") (pin "z29") (pinfunction "z29_z29") (pintype "bidirectional+no_connect"))
    )
    (net (code "344") (name "unconnected-(P3-Padz31)") (class "Default")
      (node (ref "P3") (pin "z31") (pinfunction "z31_z31") (pintype "bidirectional+no_connect"))
    )
  )
)
